# SCH_A320_OVHD_Lights_2023-04-26.net
KiCad netlist of a schematic drawn in EasyEDA
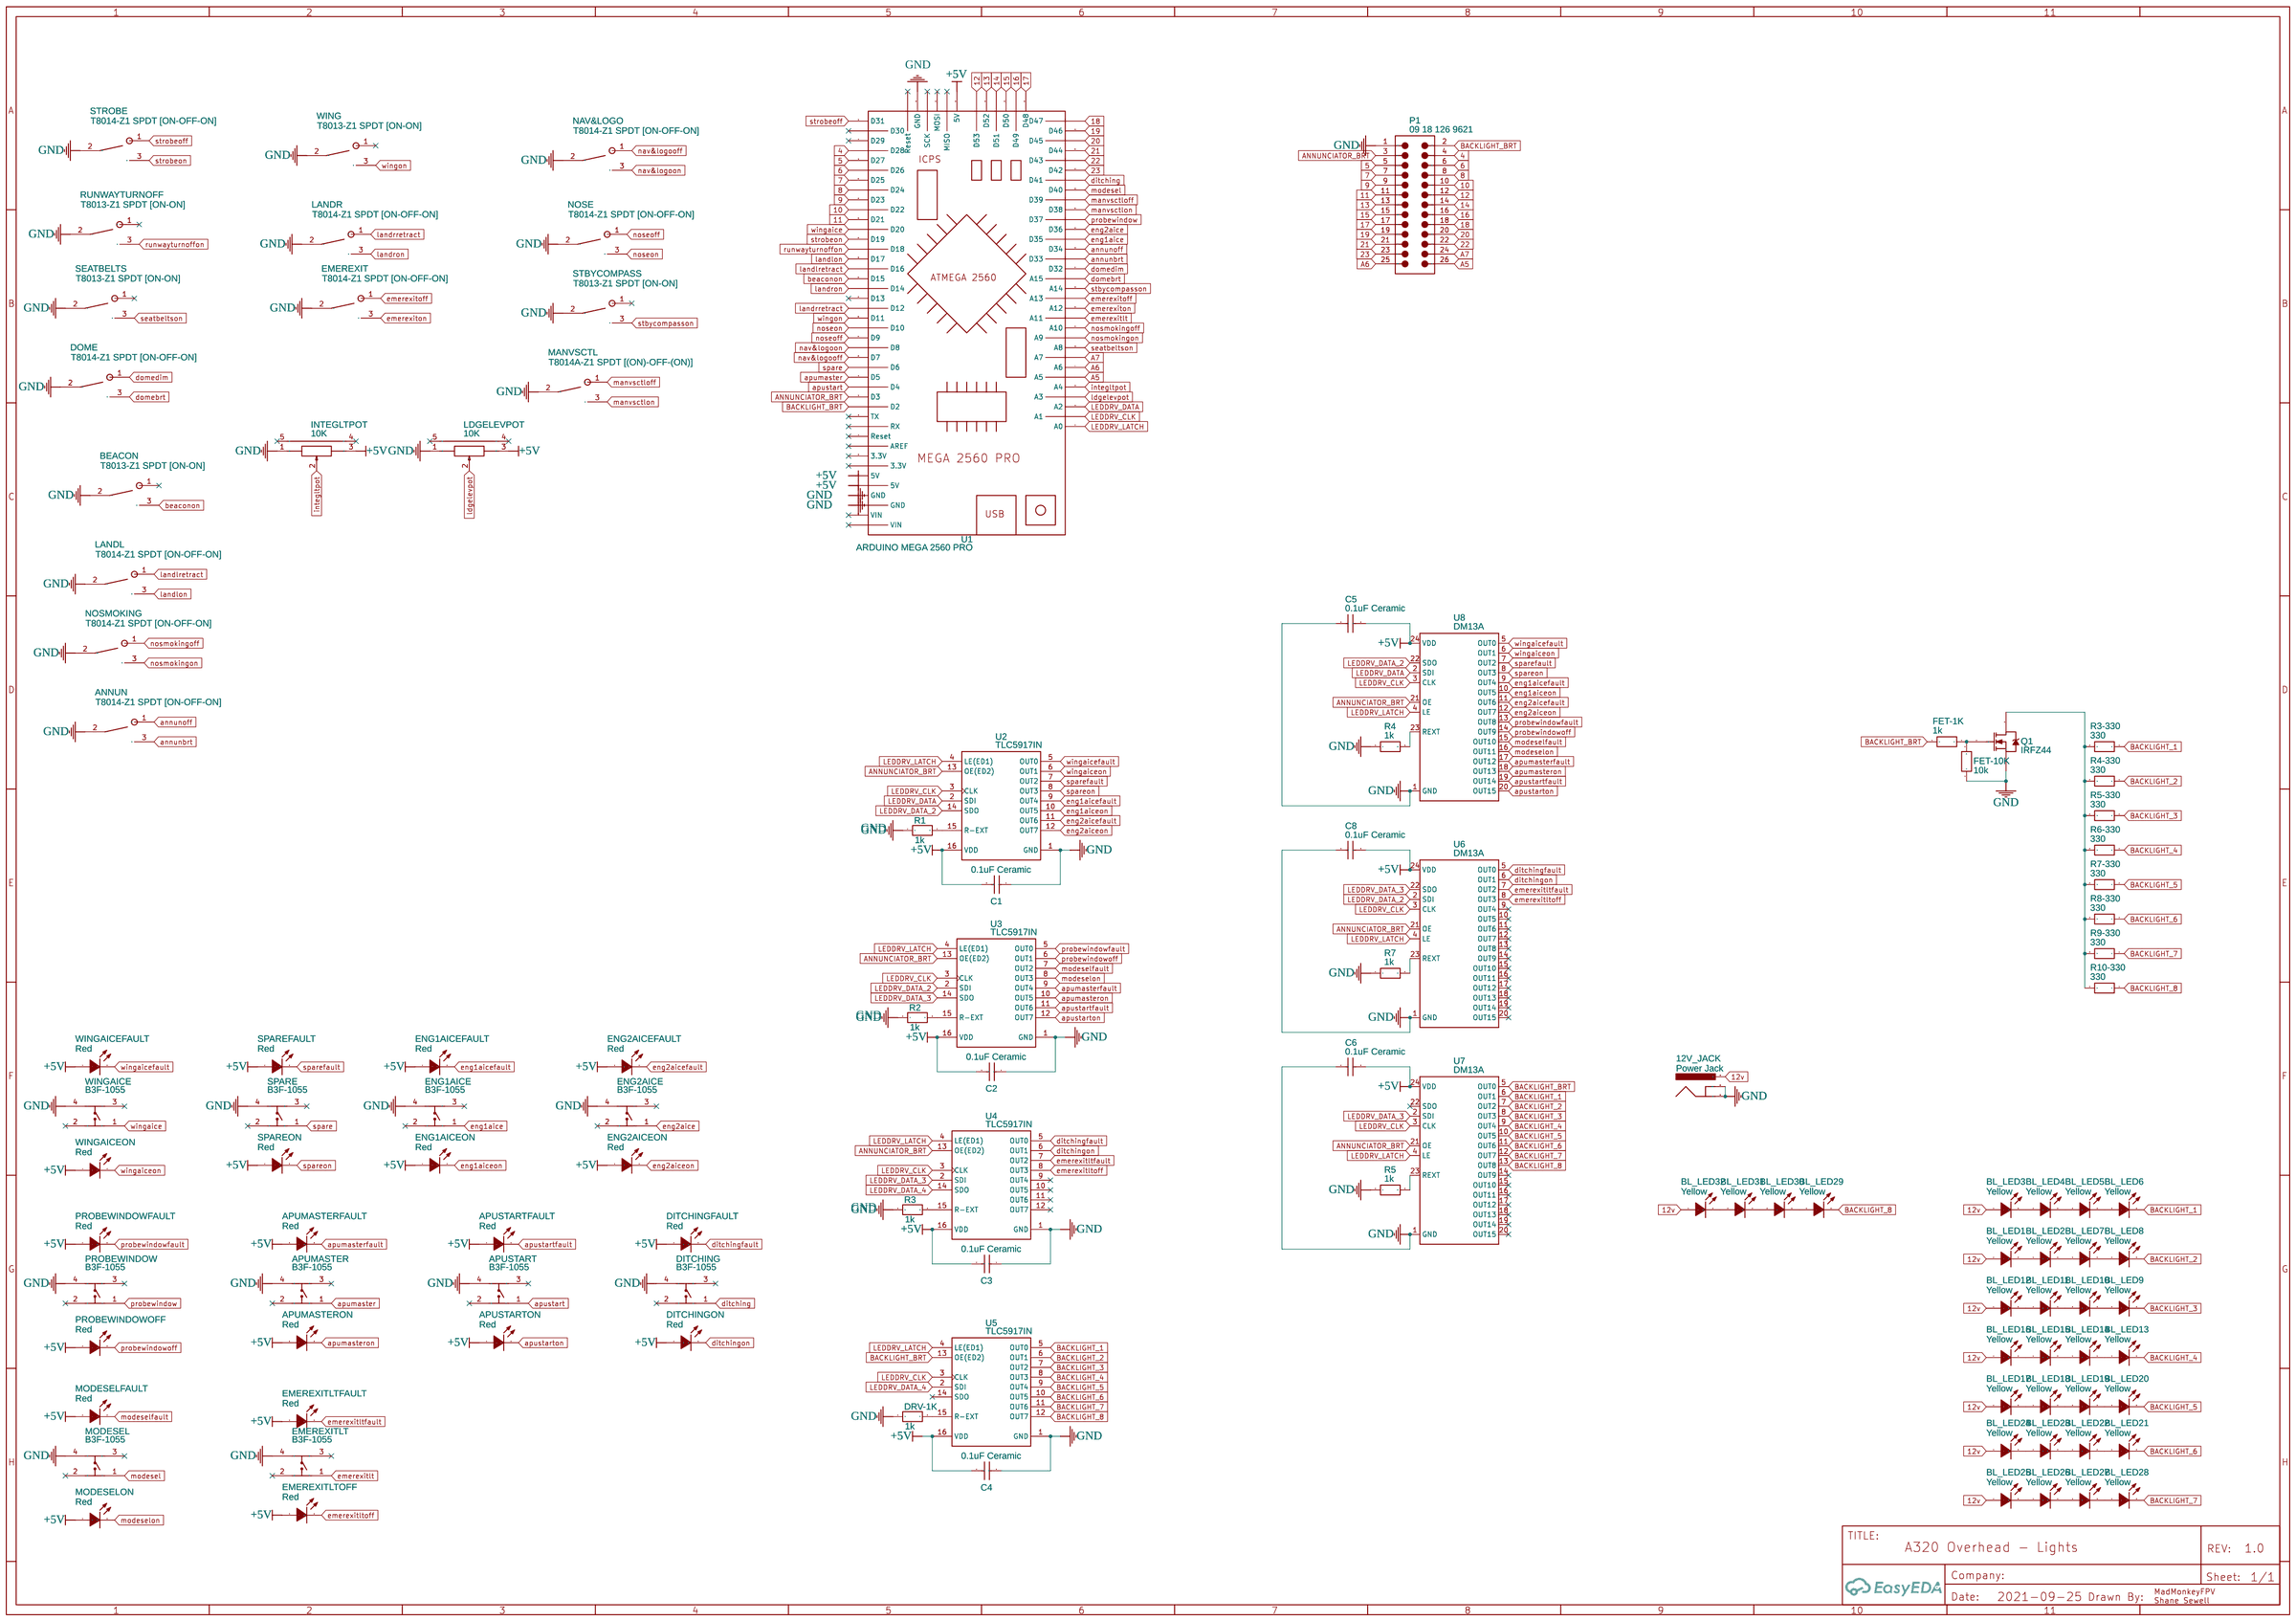
[diagram p0: schematic sheet]

(export (version "E")
  (design (tool "Eeschema 10.0.6"))
  (components
    (comp (ref "12V_JACK")
      (value "Power Jack")
      (fields (field (name "BOM_Supplier Part") "A-4118"))
      (libsource (lib "") (part "POWER_JACK"))
    )
    (comp (ref "ANNUN")
      (value "T8014-Z1 SPDT [ON-OFF-ON]")
      (libsource (lib "") (part "T8014-LK SPDT [ON-OFF-ON]_14"))
    )
    (comp (ref "APUMASTER")
      (value "B3F-1055")
      (fields (field (name "BOM_Manufacturer Part") "B3F-1052") (field (name "BOM_Supplier Part") "C87037"))
      (libsource (lib "") (part "B3F-1055_2"))
    )
    (comp (ref "APUMASTERFAULT")
      (value "Red")
      (fields
        (field (name "BOM_Manufacturer Part") "204-10SDRD/S530-A3-L")
        (field (name "BOM_Supplier Part") "C84774")
      )
      (libsource (lib "") (part "LED-TH-3mm_R_9"))
    )
    (comp (ref "APUMASTERON")
      (value "Red")
      (fields
        (field (name "BOM_Manufacturer Part") "204-10SDRD/S530-A3-L")
        (field (name "BOM_Supplier Part") "C84774")
      )
      (libsource (lib "") (part "LED-TH-3mm_R_7"))
    )
    (comp (ref "APUSTART")
      (value "B3F-1055")
      (fields (field (name "BOM_Manufacturer Part") "B3F-1052") (field (name "BOM_Supplier Part") "C87037"))
      (libsource (lib "") (part "B3F-1055_5"))
    )
    (comp (ref "APUSTARTFAULT")
      (value "Red")
      (fields
        (field (name "BOM_Manufacturer Part") "204-10SDRD/S530-A3-L")
        (field (name "BOM_Supplier Part") "C84774")
      )
      (libsource (lib "") (part "LED-TH-3mm_R"))
    )
    (comp (ref "APUSTARTON")
      (value "Red")
      (fields
        (field (name "BOM_Manufacturer Part") "204-10SDRD/S530-A3-L")
        (field (name "BOM_Supplier Part") "C84774")
      )
      (libsource (lib "") (part "LED-TH-3mm_R_14"))
    )
    (comp (ref "BEACON")
      (value "T8013-Z1 SPDT [ON-ON]")
      (libsource (lib "") (part "T8014-LK SPDT [ON-OFF-ON]_11"))
    )
    (comp (ref "BL_LED1")
      (value "Yellow")
      (fields
        (field (name "BOM_Manufacturer Part") "204-10SDRD/S530-A3-L")
        (field (name "BOM_Supplier Part") "C84774")
      )
      (libsource (lib "") (part "LED-TH-3mm_R_1"))
    )
    (comp (ref "BL_LED2")
      (value "Yellow")
      (fields
        (field (name "BOM_Manufacturer Part") "204-10SDRD/S530-A3-L")
        (field (name "BOM_Supplier Part") "C84774")
      )
      (libsource (lib "") (part "LED-TH-3mm_R_1"))
    )
    (comp (ref "BL_LED3")
      (value "Yellow")
      (fields
        (field (name "BOM_Manufacturer Part") "204-10SDRD/S530-A3-L")
        (field (name "BOM_Supplier Part") "C84774")
      )
      (libsource (lib "") (part "LED-TH-3mm_R_1"))
    )
    (comp (ref "BL_LED4")
      (value "Yellow")
      (fields
        (field (name "BOM_Manufacturer Part") "204-10SDRD/S530-A3-L")
        (field (name "BOM_Supplier Part") "C84774")
      )
      (libsource (lib "") (part "LED-TH-3mm_R_1"))
    )
    (comp (ref "BL_LED5")
      (value "Yellow")
      (fields
        (field (name "BOM_Manufacturer Part") "204-10SDRD/S530-A3-L")
        (field (name "BOM_Supplier Part") "C84774")
      )
      (libsource (lib "") (part "LED-TH-3mm_R_1"))
    )
    (comp (ref "BL_LED6")
      (value "Yellow")
      (fields
        (field (name "BOM_Manufacturer Part") "204-10SDRD/S530-A3-L")
        (field (name "BOM_Supplier Part") "C84774")
      )
      (libsource (lib "") (part "LED-TH-3mm_R_1"))
    )
    (comp (ref "BL_LED7")
      (value "Yellow")
      (fields
        (field (name "BOM_Manufacturer Part") "204-10SDRD/S530-A3-L")
        (field (name "BOM_Supplier Part") "C84774")
      )
      (libsource (lib "") (part "LED-TH-3mm_R_1"))
    )
    (comp (ref "BL_LED8")
      (value "Yellow")
      (fields
        (field (name "BOM_Manufacturer Part") "204-10SDRD/S530-A3-L")
        (field (name "BOM_Supplier Part") "C84774")
      )
      (libsource (lib "") (part "LED-TH-3mm_R_1"))
    )
    (comp (ref "BL_LED9")
      (value "Yellow")
      (fields
        (field (name "BOM_Manufacturer Part") "204-10SDRD/S530-A3-L")
        (field (name "BOM_Supplier Part") "C84774")
      )
      (libsource (lib "") (part "LED-TH-3mm_R_1"))
    )
    (comp (ref "BL_LED10")
      (value "Yellow")
      (fields
        (field (name "BOM_Manufacturer Part") "204-10SDRD/S530-A3-L")
        (field (name "BOM_Supplier Part") "C84774")
      )
      (libsource (lib "") (part "LED-TH-3mm_R_1"))
    )
    (comp (ref "BL_LED11")
      (value "Yellow")
      (fields
        (field (name "BOM_Manufacturer Part") "204-10SDRD/S530-A3-L")
        (field (name "BOM_Supplier Part") "C84774")
      )
      (libsource (lib "") (part "LED-TH-3mm_R_1"))
    )
    (comp (ref "BL_LED12")
      (value "Yellow")
      (fields
        (field (name "BOM_Manufacturer Part") "204-10SDRD/S530-A3-L")
        (field (name "BOM_Supplier Part") "C84774")
      )
      (libsource (lib "") (part "LED-TH-3mm_R_1"))
    )
    (comp (ref "BL_LED13")
      (value "Yellow")
      (fields
        (field (name "BOM_Manufacturer Part") "204-10SDRD/S530-A3-L")
        (field (name "BOM_Supplier Part") "C84774")
      )
      (libsource (lib "") (part "LED-TH-3mm_R_1"))
    )
    (comp (ref "BL_LED14")
      (value "Yellow")
      (fields
        (field (name "BOM_Manufacturer Part") "204-10SDRD/S530-A3-L")
        (field (name "BOM_Supplier Part") "C84774")
      )
      (libsource (lib "") (part "LED-TH-3mm_R_1"))
    )
    (comp (ref "BL_LED15")
      (value "Yellow")
      (fields
        (field (name "BOM_Manufacturer Part") "204-10SDRD/S530-A3-L")
        (field (name "BOM_Supplier Part") "C84774")
      )
      (libsource (lib "") (part "LED-TH-3mm_R_1"))
    )
    (comp (ref "BL_LED16")
      (value "Yellow")
      (fields
        (field (name "BOM_Manufacturer Part") "204-10SDRD/S530-A3-L")
        (field (name "BOM_Supplier Part") "C84774")
      )
      (libsource (lib "") (part "LED-TH-3mm_R_1"))
    )
    (comp (ref "BL_LED17")
      (value "Yellow")
      (fields
        (field (name "BOM_Manufacturer Part") "204-10SDRD/S530-A3-L")
        (field (name "BOM_Supplier Part") "C84774")
      )
      (libsource (lib "") (part "LED-TH-3mm_R_1"))
    )
    (comp (ref "BL_LED18")
      (value "Yellow")
      (fields
        (field (name "BOM_Manufacturer Part") "204-10SDRD/S530-A3-L")
        (field (name "BOM_Supplier Part") "C84774")
      )
      (libsource (lib "") (part "LED-TH-3mm_R_1"))
    )
    (comp (ref "BL_LED19")
      (value "Yellow")
      (fields
        (field (name "BOM_Manufacturer Part") "204-10SDRD/S530-A3-L")
        (field (name "BOM_Supplier Part") "C84774")
      )
      (libsource (lib "") (part "LED-TH-3mm_R_1"))
    )
    (comp (ref "BL_LED20")
      (value "Yellow")
      (fields
        (field (name "BOM_Manufacturer Part") "204-10SDRD/S530-A3-L")
        (field (name "BOM_Supplier Part") "C84774")
      )
      (libsource (lib "") (part "LED-TH-3mm_R_1"))
    )
    (comp (ref "BL_LED21")
      (value "Yellow")
      (fields
        (field (name "BOM_Manufacturer Part") "204-10SDRD/S530-A3-L")
        (field (name "BOM_Supplier Part") "C84774")
      )
      (libsource (lib "") (part "LED-TH-3mm_R_1"))
    )
    (comp (ref "BL_LED22")
      (value "Yellow")
      (fields
        (field (name "BOM_Manufacturer Part") "204-10SDRD/S530-A3-L")
        (field (name "BOM_Supplier Part") "C84774")
      )
      (libsource (lib "") (part "LED-TH-3mm_R_1"))
    )
    (comp (ref "BL_LED23")
      (value "Yellow")
      (fields
        (field (name "BOM_Manufacturer Part") "204-10SDRD/S530-A3-L")
        (field (name "BOM_Supplier Part") "C84774")
      )
      (libsource (lib "") (part "LED-TH-3mm_R_1"))
    )
    (comp (ref "BL_LED24")
      (value "Yellow")
      (fields
        (field (name "BOM_Manufacturer Part") "204-10SDRD/S530-A3-L")
        (field (name "BOM_Supplier Part") "C84774")
      )
      (libsource (lib "") (part "LED-TH-3mm_R_1"))
    )
    (comp (ref "BL_LED25")
      (value "Yellow")
      (fields
        (field (name "BOM_Manufacturer Part") "204-10SDRD/S530-A3-L")
        (field (name "BOM_Supplier Part") "C84774")
      )
      (libsource (lib "") (part "LED-TH-3mm_R_1"))
    )
    (comp (ref "BL_LED26")
      (value "Yellow")
      (fields
        (field (name "BOM_Manufacturer Part") "204-10SDRD/S530-A3-L")
        (field (name "BOM_Supplier Part") "C84774")
      )
      (libsource (lib "") (part "LED-TH-3mm_R_1"))
    )
    (comp (ref "BL_LED27")
      (value "Yellow")
      (fields
        (field (name "BOM_Manufacturer Part") "204-10SDRD/S530-A3-L")
        (field (name "BOM_Supplier Part") "C84774")
      )
      (libsource (lib "") (part "LED-TH-3mm_R_1"))
    )
    (comp (ref "BL_LED28")
      (value "Yellow")
      (fields
        (field (name "BOM_Manufacturer Part") "204-10SDRD/S530-A3-L")
        (field (name "BOM_Supplier Part") "C84774")
      )
      (libsource (lib "") (part "LED-TH-3mm_R_1"))
    )
    (comp (ref "BL_LED29")
      (value "Yellow")
      (fields
        (field (name "BOM_Manufacturer Part") "204-10SDRD/S530-A3-L")
        (field (name "BOM_Supplier Part") "C84774")
      )
      (libsource (lib "") (part "LED-TH-3mm_R_1"))
    )
    (comp (ref "BL_LED30")
      (value "Yellow")
      (fields
        (field (name "BOM_Manufacturer Part") "204-10SDRD/S530-A3-L")
        (field (name "BOM_Supplier Part") "C84774")
      )
      (libsource (lib "") (part "LED-TH-3mm_R_1"))
    )
    (comp (ref "BL_LED31")
      (value "Yellow")
      (fields
        (field (name "BOM_Manufacturer Part") "204-10SDRD/S530-A3-L")
        (field (name "BOM_Supplier Part") "C84774")
      )
      (libsource (lib "") (part "LED-TH-3mm_R_1"))
    )
    (comp (ref "BL_LED32")
      (value "Yellow")
      (fields
        (field (name "BOM_Manufacturer Part") "204-10SDRD/S530-A3-L")
        (field (name "BOM_Supplier Part") "C84774")
      )
      (libsource (lib "") (part "LED-TH-3mm_R_1"))
    )
    (comp (ref "C1")
      (value "0.1uF Ceramic")
      (fields (field (name "BOM_Manufacturer Part") "Capacitor_Ceramic"))
      (libsource (lib "") (part "Capacitor_Ceramic"))
    )
    (comp (ref "C2")
      (value "0.1uF Ceramic")
      (fields (field (name "BOM_Manufacturer Part") "Capacitor_Ceramic"))
      (libsource (lib "") (part "Capacitor_Ceramic"))
    )
    (comp (ref "C3")
      (value "0.1uF Ceramic")
      (fields (field (name "BOM_Manufacturer Part") "Capacitor_Ceramic"))
      (libsource (lib "") (part "Capacitor_Ceramic"))
    )
    (comp (ref "C4")
      (value "0.1uF Ceramic")
      (fields (field (name "BOM_Manufacturer Part") "Capacitor_Ceramic"))
      (libsource (lib "") (part "Capacitor_Ceramic"))
    )
    (comp (ref "C5")
      (value "0.1uF Ceramic")
      (fields (field (name "BOM_Manufacturer Part") "Capacitor_Ceramic"))
      (libsource (lib "") (part "Capacitor_Ceramic_1"))
    )
    (comp (ref "C6")
      (value "0.1uF Ceramic")
      (fields (field (name "BOM_Manufacturer Part") "Capacitor_Ceramic"))
      (libsource (lib "") (part "Capacitor_Ceramic_1"))
    )
    (comp (ref "C8")
      (value "0.1uF Ceramic")
      (fields (field (name "BOM_Manufacturer Part") "Capacitor_Ceramic"))
      (libsource (lib "") (part "Capacitor_Ceramic_1"))
    )
    (comp (ref "DITCHING")
      (value "B3F-1055")
      (fields (field (name "BOM_Manufacturer Part") "B3F-1052") (field (name "BOM_Supplier Part") "C87037"))
      (libsource (lib "") (part "B3F-1055_1"))
    )
    (comp (ref "DITCHINGFAULT")
      (value "Red")
      (fields
        (field (name "BOM_Manufacturer Part") "204-10SDRD/S530-A3-L")
        (field (name "BOM_Supplier Part") "C84774")
      )
      (libsource (lib "") (part "LED-TH-3mm_R_18"))
    )
    (comp (ref "DITCHINGON")
      (value "Red")
      (fields
        (field (name "BOM_Manufacturer Part") "204-10SDRD/S530-A3-L")
        (field (name "BOM_Supplier Part") "C84774")
      )
      (libsource (lib "") (part "LED-TH-3mm_R_19"))
    )
    (comp (ref "DOME")
      (value "T8014-Z1 SPDT [ON-OFF-ON]")
      (libsource (lib "") (part "T8014-LK SPDT [ON-OFF-ON]_8"))
    )
    (comp (ref "DRV-1K") (value "1k") (libsource (lib "") (part "R_AXIAL-0.3_EU_8")))
    (comp (ref "EMEREXIT")
      (value "T8014-Z1 SPDT [ON-OFF-ON]")
      (libsource (lib "") (part "T8014-LK SPDT [ON-OFF-ON]_2"))
    )
    (comp (ref "EMEREXITLT")
      (value "B3F-1055")
      (fields (field (name "BOM_Manufacturer Part") "B3F-1052") (field (name "BOM_Supplier Part") "C87037"))
      (libsource (lib "") (part "B3F-1055_9"))
    )
    (comp (ref "EMEREXITLTFAULT")
      (value "Red")
      (fields
        (field (name "BOM_Manufacturer Part") "204-10SDRD/S530-A3-L")
        (field (name "BOM_Supplier Part") "C84774")
      )
      (libsource (lib "") (part "LED-TH-3mm_R_12"))
    )
    (comp (ref "EMEREXITLTOFF")
      (value "Red")
      (fields
        (field (name "BOM_Manufacturer Part") "204-10SDRD/S530-A3-L")
        (field (name "BOM_Supplier Part") "C84774")
      )
      (libsource (lib "") (part "LED-TH-3mm_R_6"))
    )
    (comp (ref "ENG1AICE")
      (value "B3F-1055")
      (fields (field (name "BOM_Manufacturer Part") "B3F-1052") (field (name "BOM_Supplier Part") "C87037"))
      (libsource (lib "") (part "B3F-1055"))
    )
    (comp (ref "ENG1AICEFAULT")
      (value "Red")
      (fields
        (field (name "BOM_Manufacturer Part") "204-10SDRD/S530-A3-L")
        (field (name "BOM_Supplier Part") "C84774")
      )
      (libsource (lib "") (part "LED-TH-3mm_R_5"))
    )
    (comp (ref "ENG1AICEON")
      (value "Red")
      (fields
        (field (name "BOM_Manufacturer Part") "204-10SDRD/S530-A3-L")
        (field (name "BOM_Supplier Part") "C84774")
      )
      (libsource (lib "") (part "LED-TH-3mm_R_11"))
    )
    (comp (ref "ENG2AICE")
      (value "B3F-1055")
      (fields (field (name "BOM_Manufacturer Part") "B3F-1052") (field (name "BOM_Supplier Part") "C87037"))
      (libsource (lib "") (part "B3F-1055_6"))
    )
    (comp (ref "ENG2AICEFAULT")
      (value "Red")
      (fields
        (field (name "BOM_Manufacturer Part") "204-10SDRD/S530-A3-L")
        (field (name "BOM_Supplier Part") "C84774")
      )
      (libsource (lib "") (part "LED-TH-3mm_R_15"))
    )
    (comp (ref "ENG2AICEON")
      (value "Red")
      (fields
        (field (name "BOM_Manufacturer Part") "204-10SDRD/S530-A3-L")
        (field (name "BOM_Supplier Part") "C84774")
      )
      (libsource (lib "") (part "LED-TH-3mm_R_13"))
    )
    (comp (ref "FET-1K") (value "1k") (libsource (lib "") (part "R_AXIAL-0.3_EU_4")))
    (comp (ref "FET-10K") (value "10k") (libsource (lib "") (part "R_AXIAL-0.3_EU_11")))
    (comp (ref "INTEGLTPOT")
      (value "10K")
      (fields
        (field (name "BOM_Manufacturer Part") "RK09K1130A70")
        (field (name "BOM_Supplier Part") "C351173")
      )
      (libsource (lib "") (part "RK09K1130A70"))
    )
    (comp (ref "LANDL")
      (value "T8014-Z1 SPDT [ON-OFF-ON]")
      (libsource (lib "") (part "T8014-LK SPDT [ON-OFF-ON]_7"))
    )
    (comp (ref "LANDR")
      (value "T8014-Z1 SPDT [ON-OFF-ON]")
      (libsource (lib "") (part "T8014-LK SPDT [ON-OFF-ON]_6"))
    )
    (comp (ref "LDGELEVPOT")
      (value "10K")
      (fields
        (field (name "BOM_Manufacturer Part") "RK09K1130A70")
        (field (name "BOM_Supplier Part") "C351173")
      )
      (libsource (lib "") (part "RK09K1130A70_1"))
    )
    (comp (ref "MANVSCTL")
      (value "T8014A-Z1 SPDT [(ON)-OFF-(ON)]")
      (libsource (lib "") (part "T8014-LK SPDT [ON-OFF-ON]_4"))
    )
    (comp (ref "MODESEL")
      (value "B3F-1055")
      (fields (field (name "BOM_Manufacturer Part") "B3F-1052") (field (name "BOM_Supplier Part") "C87037"))
      (libsource (lib "") (part "B3F-1055_4"))
    )
    (comp (ref "MODESELFAULT")
      (value "Red")
      (fields
        (field (name "BOM_Manufacturer Part") "204-10SDRD/S530-A3-L")
        (field (name "BOM_Supplier Part") "C84774")
      )
      (libsource (lib "") (part "LED-TH-3mm_R_3"))
    )
    (comp (ref "MODESELON")
      (value "Red")
      (fields
        (field (name "BOM_Manufacturer Part") "204-10SDRD/S530-A3-L")
        (field (name "BOM_Supplier Part") "C84774")
      )
      (libsource (lib "") (part "LED-TH-3mm_R_16"))
    )
    (comp (ref "NAV&LOGO")
      (value "T8014-Z1 SPDT [ON-OFF-ON]")
      (libsource (lib "") (part "T8014-LK SPDT [ON-OFF-ON]_9"))
    )
    (comp (ref "NOSE")
      (value "T8014-Z1 SPDT [ON-OFF-ON]")
      (libsource (lib "") (part "T8014-LK SPDT [ON-OFF-ON]_12"))
    )
    (comp (ref "NOSMOKING")
      (value "T8014-Z1 SPDT [ON-OFF-ON]")
      (libsource (lib "") (part "T8014-LK SPDT [ON-OFF-ON]_13"))
    )
    (comp (ref "P1") (value "09 18 126 9621") (libsource (lib "") (part "09 18 126 9621")))
    (comp (ref "PROBEWINDOW")
      (value "B3F-1055")
      (fields (field (name "BOM_Manufacturer Part") "B3F-1052") (field (name "BOM_Supplier Part") "C87037"))
      (libsource (lib "") (part "B3F-1055_3"))
    )
    (comp (ref "PROBEWINDOWFAULT")
      (value "Red")
      (fields
        (field (name "BOM_Manufacturer Part") "204-10SDRD/S530-A3-L")
        (field (name "BOM_Supplier Part") "C84774")
      )
      (libsource (lib "") (part "LED-TH-3mm_R_2"))
    )
    (comp (ref "PROBEWINDOWOFF")
      (value "Red")
      (fields
        (field (name "BOM_Manufacturer Part") "204-10SDRD/S530-A3-L")
        (field (name "BOM_Supplier Part") "C84774")
      )
      (libsource (lib "") (part "LED-TH-3mm_R_17"))
    )
    (comp (ref "Q1") (value "IRFZ44") (libsource (lib "") (part "IRFZ44")))
    (comp (ref "R1") (value "1k") (libsource (lib "") (part "R_AXIAL-0.3_EU")))
    (comp (ref "R2") (value "1k") (libsource (lib "") (part "R_AXIAL-0.3_EU")))
    (comp (ref "R3") (value "1k") (libsource (lib "") (part "R_AXIAL-0.3_EU")))
    (comp (ref "R3-330") (value "330") (libsource (lib "") (part "R_AXIAL-0.3_EU_5")))
    (comp (ref "R4") (value "1k") (libsource (lib "") (part "R_AXIAL-0.3_EU")))
    (comp (ref "R4-330") (value "330") (libsource (lib "") (part "R_AXIAL-0.3_EU_2")))
    (comp (ref "R5") (value "1k") (libsource (lib "") (part "R_AXIAL-0.3_EU")))
    (comp (ref "R5-330") (value "330") (libsource (lib "") (part "R_AXIAL-0.3_EU_7")))
    (comp (ref "R6-330") (value "330") (libsource (lib "") (part "R_AXIAL-0.3_EU_9")))
    (comp (ref "R7") (value "1k") (libsource (lib "") (part "R_AXIAL-0.3_EU")))
    (comp (ref "R7-330") (value "330") (libsource (lib "") (part "R_AXIAL-0.3_EU_1")))
    (comp (ref "R8-330") (value "330") (libsource (lib "") (part "R_AXIAL-0.3_EU_3")))
    (comp (ref "R9-330") (value "330") (libsource (lib "") (part "R_AXIAL-0.3_EU_10")))
    (comp (ref "R10-330") (value "330") (libsource (lib "") (part "R_AXIAL-0.3_EU_6")))
    (comp (ref "RUNWAYTURNOFF")
      (value "T8013-Z1 SPDT [ON-ON]")
      (libsource (lib "") (part "T8014-LK SPDT [ON-OFF-ON]_5"))
    )
    (comp (ref "SEATBELTS")
      (value "T8013-Z1 SPDT [ON-ON]")
      (libsource (lib "") (part "T8014-LK SPDT [ON-OFF-ON]"))
    )
    (comp (ref "SPARE")
      (value "B3F-1055")
      (fields (field (name "BOM_Manufacturer Part") "B3F-1052") (field (name "BOM_Supplier Part") "C87037"))
      (libsource (lib "") (part "B3F-1055_8"))
    )
    (comp (ref "SPAREFAULT")
      (value "Red")
      (fields
        (field (name "BOM_Manufacturer Part") "204-10SDRD/S530-A3-L")
        (field (name "BOM_Supplier Part") "C84774")
      )
      (libsource (lib "") (part "LED-TH-3mm_R_4"))
    )
    (comp (ref "SPAREON")
      (value "Red")
      (fields
        (field (name "BOM_Manufacturer Part") "204-10SDRD/S530-A3-L")
        (field (name "BOM_Supplier Part") "C84774")
      )
      (libsource (lib "") (part "LED-TH-3mm_R_10"))
    )
    (comp (ref "STBYCOMPASS")
      (value "T8013-Z1 SPDT [ON-ON]")
      (libsource (lib "") (part "T8014-LK SPDT [ON-OFF-ON]_3"))
    )
    (comp (ref "STROBE")
      (value "T8014-Z1 SPDT [ON-OFF-ON]")
      (libsource (lib "") (part "T8014-LK SPDT [ON-OFF-ON]_10"))
    )
    (comp (ref "U1")
      (value "ARDUINO MEGA 2560 PRO")
      (fields (field (name "BOM_Manufacturer Part") "Arduino Mega 2560 Pro Mini"))
      (libsource (lib "") (part "ARDUINO MEGA 2560 PRO"))
    )
    (comp (ref "U2") (value "TLC5917IN") (libsource (lib "") (part "TLC5917IN")))
    (comp (ref "U3") (value "TLC5917IN") (libsource (lib "") (part "TLC5917IN")))
    (comp (ref "U4") (value "TLC5917IN") (libsource (lib "") (part "TLC5917IN")))
    (comp (ref "U5") (value "TLC5917IN") (libsource (lib "") (part "TLC5917IN")))
    (comp (ref "U6") (value "DM13A") (libsource (lib "") (part "DM13A")))
    (comp (ref "U7") (value "DM13A") (libsource (lib "") (part "DM13A")))
    (comp (ref "U8") (value "DM13A") (libsource (lib "") (part "DM13A")))
    (comp (ref "WING")
      (value "T8013-Z1 SPDT [ON-ON]")
      (libsource (lib "") (part "T8014-LK SPDT [ON-OFF-ON]_1"))
    )
    (comp (ref "WINGAICE")
      (value "B3F-1055")
      (fields (field (name "BOM_Manufacturer Part") "B3F-1052") (field (name "BOM_Supplier Part") "C87037"))
      (libsource (lib "") (part "B3F-1055_7"))
    )
    (comp (ref "WINGAICEFAULT")
      (value "Red")
      (fields
        (field (name "BOM_Manufacturer Part") "204-10SDRD/S530-A3-L")
        (field (name "BOM_Supplier Part") "C84774")
      )
      (libsource (lib "") (part "LED-TH-3mm_R_20"))
    )
    (comp (ref "WINGAICEON")
      (value "Red")
      (fields
        (field (name "BOM_Manufacturer Part") "204-10SDRD/S530-A3-L")
        (field (name "BOM_Supplier Part") "C84774")
      )
      (libsource (lib "") (part "LED-TH-3mm_R_8"))
    )
  )
  (nets
    (net (code "1") (name "+5V") (class "Default")
      (node (ref "APUMASTERFAULT") (pin "1") (pinfunction "1_1") (pintype "unspecified"))
      (node (ref "APUMASTERON") (pin "1") (pinfunction "1_1") (pintype "unspecified"))
      (node (ref "APUSTARTFAULT") (pin "1") (pinfunction "1_1") (pintype "unspecified"))
      (node (ref "APUSTARTON") (pin "1") (pinfunction "1_1") (pintype "unspecified"))
      (node (ref "C1") (pin "2") (pinfunction "2_2") (pintype "unspecified"))
      (node (ref "C2") (pin "2") (pinfunction "2_2") (pintype "unspecified"))
      (node (ref "C3") (pin "2") (pinfunction "2_2") (pintype "unspecified"))
      (node (ref "C4") (pin "2") (pinfunction "2_2") (pintype "unspecified"))
      (node (ref "C5") (pin "2") (pinfunction "2_2") (pintype "unspecified"))
      (node (ref "C6") (pin "2") (pinfunction "2_2") (pintype "unspecified"))
      (node (ref "C8") (pin "2") (pinfunction "2_2") (pintype "unspecified"))
      (node (ref "DITCHINGFAULT") (pin "1") (pinfunction "1_1") (pintype "unspecified"))
      (node (ref "DITCHINGON") (pin "1") (pinfunction "1_1") (pintype "unspecified"))
      (node (ref "EMEREXITLTFAULT") (pin "1") (pinfunction "1_1") (pintype "unspecified"))
      (node (ref "EMEREXITLTOFF") (pin "1") (pinfunction "1_1") (pintype "unspecified"))
      (node (ref "ENG1AICEFAULT") (pin "1") (pinfunction "1_1") (pintype "unspecified"))
      (node (ref "ENG1AICEON") (pin "1") (pinfunction "1_1") (pintype "unspecified"))
      (node (ref "ENG2AICEFAULT") (pin "1") (pinfunction "1_1") (pintype "unspecified"))
      (node (ref "ENG2AICEON") (pin "1") (pinfunction "1_1") (pintype "unspecified"))
      (node (ref "INTEGLTPOT") (pin "3") (pinfunction "3_3") (pintype "unspecified"))
      (node (ref "LDGELEVPOT") (pin "3") (pinfunction "3_3") (pintype "unspecified"))
      (node (ref "MODESELFAULT") (pin "1") (pinfunction "1_1") (pintype "unspecified"))
      (node (ref "MODESELON") (pin "1") (pinfunction "1_1") (pintype "unspecified"))
      (node (ref "PROBEWINDOWFAULT") (pin "1") (pinfunction "1_1") (pintype "unspecified"))
      (node (ref "PROBEWINDOWOFF") (pin "1") (pinfunction "1_1") (pintype "unspecified"))
      (node (ref "SPAREFAULT") (pin "1") (pinfunction "1_1") (pintype "unspecified"))
      (node (ref "SPAREON") (pin "1") (pinfunction "1_1") (pintype "unspecified"))
      (node (ref "U1") (pin "39") (pinfunction "5V_39") (pintype "unspecified"))
      (node (ref "U1") (pin "81") (pinfunction "5V_81") (pintype "unspecified"))
      (node (ref "U1") (pin "82") (pinfunction "5V_82") (pintype "unspecified"))
      (node (ref "U2") (pin "16") (pinfunction "VDD_16") (pintype "passive"))
      (node (ref "U3") (pin "16") (pinfunction "VDD_16") (pintype "passive"))
      (node (ref "U4") (pin "16") (pinfunction "VDD_16") (pintype "passive"))
      (node (ref "U5") (pin "16") (pinfunction "VDD_16") (pintype "passive"))
      (node (ref "U6") (pin "24") (pinfunction "VDD_24") (pintype "unspecified"))
      (node (ref "U7") (pin "24") (pinfunction "VDD_24") (pintype "unspecified"))
      (node (ref "U8") (pin "24") (pinfunction "VDD_24") (pintype "unspecified"))
      (node (ref "WINGAICEFAULT") (pin "1") (pinfunction "1_1") (pintype "unspecified"))
      (node (ref "WINGAICEON") (pin "1") (pinfunction "1_1") (pintype "unspecified"))
    )
    (net (code "2") (name "4") (class "Default")
      (node (ref "P1") (pin "4") (pinfunction "4_4") (pintype "unspecified"))
      (node (ref "U1") (pin "48") (pinfunction "D28_48") (pintype "unspecified"))
    )
    (net (code "3") (name "5") (class "Default")
      (node (ref "P1") (pin "5") (pinfunction "5_5") (pintype "unspecified"))
      (node (ref "U1") (pin "49") (pinfunction "D27_49") (pintype "unspecified"))
    )
    (net (code "4") (name "6") (class "Default")
      (node (ref "P1") (pin "6") (pinfunction "6_6") (pintype "unspecified"))
      (node (ref "U1") (pin "50") (pinfunction "D26_50") (pintype "unspecified"))
    )
    (net (code "5") (name "7") (class "Default")
      (node (ref "P1") (pin "7") (pinfunction "7_7") (pintype "unspecified"))
      (node (ref "U1") (pin "51") (pinfunction "D25_51") (pintype "unspecified"))
    )
    (net (code "6") (name "8") (class "Default")
      (node (ref "P1") (pin "8") (pinfunction "8_8") (pintype "unspecified"))
      (node (ref "U1") (pin "52") (pinfunction "D24_52") (pintype "unspecified"))
    )
    (net (code "7") (name "9") (class "Default")
      (node (ref "P1") (pin "9") (pinfunction "9_9") (pintype "unspecified"))
      (node (ref "U1") (pin "53") (pinfunction "D23_53") (pintype "unspecified"))
    )
    (net (code "8") (name "10") (class "Default")
      (node (ref "P1") (pin "10") (pinfunction "10_10") (pintype "unspecified"))
      (node (ref "U1") (pin "54") (pinfunction "D22_54") (pintype "unspecified"))
    )
    (net (code "9") (name "11") (class "Default")
      (node (ref "P1") (pin "11") (pinfunction "11_11") (pintype "unspecified"))
      (node (ref "U1") (pin "55") (pinfunction "D21_55") (pintype "unspecified"))
    )
    (net (code "10") (name "12") (class "Default")
      (node (ref "P1") (pin "12") (pinfunction "12_12") (pintype "unspecified"))
      (node (ref "U1") (pin "38") (pinfunction "D53_38") (pintype "unspecified"))
    )
    (net (code "11") (name "12v") (class "Default")
      (node (ref "12V_JACK") (pin "PWR") (pinfunction "PWR_PWR") (pintype "unspecified"))
      (node (ref "BL_LED1") (pin "1") (pinfunction "1_1") (pintype "unspecified"))
      (node (ref "BL_LED12") (pin "1") (pinfunction "1_1") (pintype "unspecified"))
      (node (ref "BL_LED16") (pin "1") (pinfunction "1_1") (pintype "unspecified"))
      (node (ref "BL_LED17") (pin "1") (pinfunction "1_1") (pintype "unspecified"))
      (node (ref "BL_LED24") (pin "1") (pinfunction "1_1") (pintype "unspecified"))
      (node (ref "BL_LED25") (pin "1") (pinfunction "1_1") (pintype "unspecified"))
      (node (ref "BL_LED3") (pin "1") (pinfunction "1_1") (pintype "unspecified"))
      (node (ref "BL_LED32") (pin "1") (pinfunction "1_1") (pintype "unspecified"))
    )
    (net (code "12") (name "13") (class "Default")
      (node (ref "P1") (pin "13") (pinfunction "13_13") (pintype "unspecified"))
      (node (ref "U1") (pin "37") (pinfunction "D52_37") (pintype "unspecified"))
    )
    (net (code "13") (name "14") (class "Default")
      (node (ref "P1") (pin "14") (pinfunction "14_14") (pintype "unspecified"))
      (node (ref "U1") (pin "36") (pinfunction "D51_36") (pintype "unspecified"))
    )
    (net (code "14") (name "15") (class "Default")
      (node (ref "P1") (pin "15") (pinfunction "15_15") (pintype "unspecified"))
      (node (ref "U1") (pin "35") (pinfunction "D50_35") (pintype "unspecified"))
    )
    (net (code "15") (name "16") (class "Default")
      (node (ref "P1") (pin "16") (pinfunction "16_16") (pintype "unspecified"))
      (node (ref "U1") (pin "34") (pinfunction "D49_34") (pintype "unspecified"))
    )
    (net (code "16") (name "17") (class "Default")
      (node (ref "P1") (pin "17") (pinfunction "17_17") (pintype "unspecified"))
      (node (ref "U1") (pin "33") (pinfunction "D48_33") (pintype "unspecified"))
    )
    (net (code "17") (name "18") (class "Default")
      (node (ref "P1") (pin "18") (pinfunction "18_18") (pintype "unspecified"))
      (node (ref "U1") (pin "32") (pinfunction "D47_32") (pintype "unspecified"))
    )
    (net (code "18") (name "19") (class "Default")
      (node (ref "P1") (pin "19") (pinfunction "19_19") (pintype "unspecified"))
      (node (ref "U1") (pin "31") (pinfunction "D46_31") (pintype "unspecified"))
    )
    (net (code "19") (name "20") (class "Default")
      (node (ref "P1") (pin "20") (pinfunction "20_20") (pintype "unspecified"))
      (node (ref "U1") (pin "30") (pinfunction "D45_30") (pintype "unspecified"))
    )
    (net (code "20") (name "21") (class "Default")
      (node (ref "P1") (pin "21") (pinfunction "21_21") (pintype "unspecified"))
      (node (ref "U1") (pin "29") (pinfunction "D44_29") (pintype "unspecified"))
    )
    (net (code "21") (name "22") (class "Default")
      (node (ref "P1") (pin "22") (pinfunction "22_22") (pintype "unspecified"))
      (node (ref "U1") (pin "28") (pinfunction "D43_28") (pintype "unspecified"))
    )
    (net (code "22") (name "23") (class "Default")
      (node (ref "P1") (pin "23") (pinfunction "23_23") (pintype "unspecified"))
      (node (ref "U1") (pin "27") (pinfunction "D42_27") (pintype "unspecified"))
    )
    (net (code "23") (name "A5") (class "Default")
      (node (ref "P1") (pin "26") (pinfunction "A5_26") (pintype "unspecified"))
      (node (ref "U1") (pin "6") (pinfunction "A5_6") (pintype "unspecified"))
    )
    (net (code "24") (name "A6") (class "Default")
      (node (ref "P1") (pin "25") (pinfunction "A6_25") (pintype "unspecified"))
      (node (ref "U1") (pin "7") (pinfunction "A6_7") (pintype "unspecified"))
    )
    (net (code "25") (name "A7") (class "Default")
      (node (ref "P1") (pin "24") (pinfunction "A7_24") (pintype "unspecified"))
      (node (ref "U1") (pin "8") (pinfunction "A7_8") (pintype "unspecified"))
    )
    (net (code "26") (name "ANNUNCIATOR_BRT") (class "Default")
      (node (ref "P1") (pin "3") (pinfunction "3_3") (pintype "unspecified"))
      (node (ref "U1") (pin "73") (pinfunction "D3_73") (pintype "unspecified"))
      (node (ref "U2") (pin "13") (pinfunction "OE(ED2)_13") (pintype "unspecified"))
      (node (ref "U3") (pin "13") (pinfunction "OE(ED2)_13") (pintype "unspecified"))
      (node (ref "U4") (pin "13") (pinfunction "OE(ED2)_13") (pintype "unspecified"))
      (node (ref "U6") (pin "21") (pinfunction "OE_21") (pintype "unspecified"))
      (node (ref "U7") (pin "21") (pinfunction "OE_21") (pintype "unspecified"))
      (node (ref "U8") (pin "21") (pinfunction "OE_21") (pintype "unspecified"))
    )
    (net (code "27") (name "BACKLIGHT_1") (class "Default")
      (node (ref "BL_LED6") (pin "2") (pinfunction "2_2") (pintype "unspecified"))
      (node (ref "R3-330") (pin "1") (pinfunction "1_1") (pintype "unspecified"))
      (node (ref "U5") (pin "5") (pinfunction "OUT0_5") (pintype "output"))
      (node (ref "U7") (pin "6") (pinfunction "OUT1_6") (pintype "unspecified"))
    )
    (net (code "28") (name "BACKLIGHT_2") (class "Default")
      (node (ref "BL_LED8") (pin "2") (pinfunction "2_2") (pintype "unspecified"))
      (node (ref "R4-330") (pin "1") (pinfunction "1_1") (pintype "unspecified"))
      (node (ref "U5") (pin "6") (pinfunction "OUT1_6") (pintype "output"))
      (node (ref "U7") (pin "7") (pinfunction "OUT2_7") (pintype "unspecified"))
    )
    (net (code "29") (name "BACKLIGHT_3") (class "Default")
      (node (ref "BL_LED9") (pin "2") (pinfunction "2_2") (pintype "unspecified"))
      (node (ref "R5-330") (pin "1") (pinfunction "1_1") (pintype "unspecified"))
      (node (ref "U5") (pin "7") (pinfunction "OUT2_7") (pintype "output"))
      (node (ref "U7") (pin "8") (pinfunction "OUT3_8") (pintype "unspecified"))
    )
    (net (code "30") (name "BACKLIGHT_4") (class "Default")
      (node (ref "BL_LED13") (pin "2") (pinfunction "2_2") (pintype "unspecified"))
      (node (ref "R6-330") (pin "1") (pinfunction "1_1") (pintype "unspecified"))
      (node (ref "U5") (pin "8") (pinfunction "OUT3_8") (pintype "output"))
      (node (ref "U7") (pin "9") (pinfunction "OUT4_9") (pintype "unspecified"))
    )
    (net (code "31") (name "BACKLIGHT_5") (class "Default")
      (node (ref "BL_LED20") (pin "2") (pinfunction "2_2") (pintype "unspecified"))
      (node (ref "R7-330") (pin "1") (pinfunction "1_1") (pintype "unspecified"))
      (node (ref "U5") (pin "9") (pinfunction "OUT4_9") (pintype "output"))
      (node (ref "U7") (pin "10") (pinfunction "OUT5_10") (pintype "unspecified"))
    )
    (net (code "32") (name "BACKLIGHT_6") (class "Default")
      (node (ref "BL_LED21") (pin "2") (pinfunction "2_2") (pintype "unspecified"))
      (node (ref "R8-330") (pin "1") (pinfunction "1_1") (pintype "unspecified"))
      (node (ref "U5") (pin "10") (pinfunction "OUT5_10") (pintype "output"))
      (node (ref "U7") (pin "11") (pinfunction "OUT6_11") (pintype "unspecified"))
    )
    (net (code "33") (name "BACKLIGHT_7") (class "Default")
      (node (ref "BL_LED28") (pin "2") (pinfunction "2_2") (pintype "unspecified"))
      (node (ref "R9-330") (pin "1") (pinfunction "1_1") (pintype "unspecified"))
      (node (ref "U5") (pin "11") (pinfunction "OUT6_11") (pintype "output"))
      (node (ref "U7") (pin "12") (pinfunction "OUT7_12") (pintype "unspecified"))
    )
    (net (code "34") (name "BACKLIGHT_8") (class "Default")
      (node (ref "BL_LED29") (pin "2") (pinfunction "2_2") (pintype "unspecified"))
      (node (ref "R10-330") (pin "1") (pinfunction "1_1") (pintype "unspecified"))
      (node (ref "U5") (pin "12") (pinfunction "OUT7_12") (pintype "output"))
      (node (ref "U7") (pin "13") (pinfunction "OUT8_13") (pintype "unspecified"))
    )
    (net (code "35") (name "BACKLIGHT_BRT") (class "Default")
      (node (ref "FET-1K") (pin "2") (pinfunction "2_2") (pintype "unspecified"))
      (node (ref "P1") (pin "2") (pinfunction "2_2") (pintype "unspecified"))
      (node (ref "U1") (pin "74") (pinfunction "D2_74") (pintype "unspecified"))
      (node (ref "U5") (pin "13") (pinfunction "OE(ED2)_13") (pintype "unspecified"))
      (node (ref "U7") (pin "5") (pinfunction "OUT0_5") (pintype "unspecified"))
    )
    (net (code "36") (name "GND") (class "Default")
      (node (ref "12V_JACK") (pin "GND") (pinfunction "GND_GND") (pintype "unspecified"))
      (node (ref "12V_JACK") (pin "GNDBREAK") (pinfunction "GNDBREAK_GNDBREAK") (pintype "unspecified"))
      (node (ref "ANNUN") (pin "2") (pinfunction "2_2") (pintype "input"))
      (node (ref "APUMASTER") (pin "4") (pinfunction "4_4") (pintype "unspecified"))
      (node (ref "APUSTART") (pin "4") (pinfunction "4_4") (pintype "unspecified"))
      (node (ref "BEACON") (pin "2") (pinfunction "2_2") (pintype "input"))
      (node (ref "C1") (pin "1") (pinfunction "1_1") (pintype "unspecified"))
      (node (ref "C2") (pin "1") (pinfunction "1_1") (pintype "unspecified"))
      (node (ref "C3") (pin "1") (pinfunction "1_1") (pintype "unspecified"))
      (node (ref "C4") (pin "1") (pinfunction "1_1") (pintype "unspecified"))
      (node (ref "C5") (pin "1") (pinfunction "1_1") (pintype "unspecified"))
      (node (ref "C6") (pin "1") (pinfunction "1_1") (pintype "unspecified"))
      (node (ref "C8") (pin "1") (pinfunction "1_1") (pintype "unspecified"))
      (node (ref "DITCHING") (pin "4") (pinfunction "4_4") (pintype "unspecified"))
      (node (ref "DOME") (pin "2") (pinfunction "2_2") (pintype "input"))
      (node (ref "DRV-1K") (pin "1") (pinfunction "1_1") (pintype "unspecified"))
      (node (ref "EMEREXIT") (pin "2") (pinfunction "2_2") (pintype "input"))
      (node (ref "EMEREXITLT") (pin "4") (pinfunction "4_4") (pintype "unspecified"))
      (node (ref "ENG1AICE") (pin "4") (pinfunction "4_4") (pintype "unspecified"))
      (node (ref "ENG2AICE") (pin "4") (pinfunction "4_4") (pintype "unspecified"))
      (node (ref "FET-10K") (pin "1") (pinfunction "1_1") (pintype "unspecified"))
      (node (ref "INTEGLTPOT") (pin "1") (pinfunction "1_1") (pintype "unspecified"))
      (node (ref "LANDL") (pin "2") (pinfunction "2_2") (pintype "input"))
      (node (ref "LANDR") (pin "2") (pinfunction "2_2") (pintype "input"))
      (node (ref "LDGELEVPOT") (pin "1") (pinfunction "1_1") (pintype "unspecified"))
      (node (ref "MANVSCTL") (pin "2") (pinfunction "2_2") (pintype "input"))
      (node (ref "MODESEL") (pin "4") (pinfunction "4_4") (pintype "unspecified"))
      (node (ref "NAV&LOGO") (pin "2") (pinfunction "2_2") (pintype "input"))
      (node (ref "NOSE") (pin "2") (pinfunction "2_2") (pintype "input"))
      (node (ref "NOSMOKING") (pin "2") (pinfunction "2_2") (pintype "input"))
      (node (ref "P1") (pin "1") (pinfunction "GND_1") (pintype "unspecified"))
      (node (ref "PROBEWINDOW") (pin "4") (pinfunction "4_4") (pintype "unspecified"))
      (node (ref "Q1") (pin "3") (pinfunction "S_3") (pintype "unspecified"))
      (node (ref "R1") (pin "1") (pinfunction "1_1") (pintype "unspecified"))
      (node (ref "R2") (pin "1") (pinfunction "1_1") (pintype "unspecified"))
      (node (ref "R3") (pin "1") (pinfunction "1_1") (pintype "unspecified"))
      (node (ref "R4") (pin "1") (pinfunction "1_1") (pintype "unspecified"))
      (node (ref "R5") (pin "1") (pinfunction "1_1") (pintype "unspecified"))
      (node (ref "R7") (pin "1") (pinfunction "1_1") (pintype "unspecified"))
      (node (ref "RUNWAYTURNOFF") (pin "2") (pinfunction "2_2") (pintype "input"))
      (node (ref "SEATBELTS") (pin "2") (pinfunction "2_2") (pintype "input"))
      (node (ref "SPARE") (pin "4") (pinfunction "4_4") (pintype "unspecified"))
      (node (ref "STBYCOMPASS") (pin "2") (pinfunction "2_2") (pintype "input"))
      (node (ref "STROBE") (pin "2") (pinfunction "2_2") (pintype "input"))
      (node (ref "U1") (pin "43") (pinfunction "GND_43") (pintype "unspecified"))
      (node (ref "U1") (pin "83") (pinfunction "GND_83") (pintype "unspecified"))
      (node (ref "U1") (pin "84") (pinfunction "GND_84") (pintype "unspecified"))
      (node (ref "U2") (pin "1") (pinfunction "GND_1") (pintype "passive"))
      (node (ref "U3") (pin "1") (pinfunction "GND_1") (pintype "passive"))
      (node (ref "U4") (pin "1") (pinfunction "GND_1") (pintype "passive"))
      (node (ref "U5") (pin "1") (pinfunction "GND_1") (pintype "passive"))
      (node (ref "U6") (pin "1") (pinfunction "GND_1") (pintype "unspecified"))
      (node (ref "U7") (pin "1") (pinfunction "GND_1") (pintype "unspecified"))
      (node (ref "U8") (pin "1") (pinfunction "GND_1") (pintype "unspecified"))
      (node (ref "WING") (pin "2") (pinfunction "2_2") (pintype "input"))
      (node (ref "WINGAICE") (pin "4") (pinfunction "4_4") (pintype "unspecified"))
    )
    (net (code "37") (name "LEDDRV_CLK") (class "Default")
      (node (ref "U1") (pin "2") (pinfunction "A1_2") (pintype "unspecified"))
      (node (ref "U2") (pin "3") (pinfunction "CLK_3") (pintype "unspecified"))
      (node (ref "U3") (pin "3") (pinfunction "CLK_3") (pintype "unspecified"))
      (node (ref "U4") (pin "3") (pinfunction "CLK_3") (pintype "unspecified"))
      (node (ref "U5") (pin "3") (pinfunction "CLK_3") (pintype "unspecified"))
      (node (ref "U6") (pin "3") (pinfunction "CLK_3") (pintype "unspecified"))
      (node (ref "U7") (pin "3") (pinfunction "CLK_3") (pintype "unspecified"))
      (node (ref "U8") (pin "3") (pinfunction "CLK_3") (pintype "unspecified"))
    )
    (net (code "38") (name "LEDDRV_DATA") (class "Default")
      (node (ref "U1") (pin "3") (pinfunction "A2_3") (pintype "unspecified"))
      (node (ref "U2") (pin "2") (pinfunction "SDI_2") (pintype "unspecified"))
      (node (ref "U8") (pin "2") (pinfunction "SDI_2") (pintype "unspecified"))
    )
    (net (code "39") (name "LEDDRV_DATA_2") (class "Default")
      (node (ref "U2") (pin "14") (pinfunction "SDO_14") (pintype "output"))
      (node (ref "U3") (pin "2") (pinfunction "SDI_2") (pintype "unspecified"))
      (node (ref "U6") (pin "2") (pinfunction "SDI_2") (pintype "unspecified"))
      (node (ref "U8") (pin "22") (pinfunction "SDO_22") (pintype "unspecified"))
    )
    (net (code "40") (name "LEDDRV_DATA_3") (class "Default")
      (node (ref "U3") (pin "14") (pinfunction "SDO_14") (pintype "output"))
      (node (ref "U4") (pin "2") (pinfunction "SDI_2") (pintype "unspecified"))
      (node (ref "U6") (pin "22") (pinfunction "SDO_22") (pintype "unspecified"))
      (node (ref "U7") (pin "2") (pinfunction "SDI_2") (pintype "unspecified"))
    )
    (net (code "41") (name "LEDDRV_DATA_4") (class "Default")
      (node (ref "U4") (pin "14") (pinfunction "SDO_14") (pintype "output"))
      (node (ref "U5") (pin "2") (pinfunction "SDI_2") (pintype "unspecified"))
    )
    (net (code "42") (name "LEDDRV_LATCH") (class "Default")
      (node (ref "U1") (pin "1") (pinfunction "A0_1") (pintype "unspecified"))
      (node (ref "U2") (pin "4") (pinfunction "LE(ED1)_4") (pintype "unspecified"))
      (node (ref "U3") (pin "4") (pinfunction "LE(ED1)_4") (pintype "unspecified"))
      (node (ref "U4") (pin "4") (pinfunction "LE(ED1)_4") (pintype "unspecified"))
      (node (ref "U5") (pin "4") (pinfunction "LE(ED1)_4") (pintype "unspecified"))
      (node (ref "U6") (pin "4") (pinfunction "LE_4") (pintype "unspecified"))
      (node (ref "U7") (pin "4") (pinfunction "LE_4") (pintype "unspecified"))
      (node (ref "U8") (pin "4") (pinfunction "LE_4") (pintype "unspecified"))
    )
    (net (code "43") (name "Net-(BL_LED1-Pad2)") (class "Default")
      (node (ref "BL_LED1") (pin "2") (pinfunction "2_2") (pintype "unspecified"))
      (node (ref "BL_LED2") (pin "1") (pinfunction "1_1") (pintype "unspecified"))
    )
    (net (code "44") (name "Net-(BL_LED2-Pad2)") (class "Default")
      (node (ref "BL_LED2") (pin "2") (pinfunction "2_2") (pintype "unspecified"))
      (node (ref "BL_LED7") (pin "1") (pinfunction "1_1") (pintype "unspecified"))
    )
    (net (code "45") (name "Net-(BL_LED3-Pad2)") (class "Default")
      (node (ref "BL_LED3") (pin "2") (pinfunction "2_2") (pintype "unspecified"))
      (node (ref "BL_LED4") (pin "1") (pinfunction "1_1") (pintype "unspecified"))
    )
    (net (code "46") (name "Net-(BL_LED4-Pad2)") (class "Default")
      (node (ref "BL_LED4") (pin "2") (pinfunction "2_2") (pintype "unspecified"))
      (node (ref "BL_LED5") (pin "1") (pinfunction "1_1") (pintype "unspecified"))
    )
    (net (code "47") (name "Net-(BL_LED5-Pad2)") (class "Default")
      (node (ref "BL_LED5") (pin "2") (pinfunction "2_2") (pintype "unspecified"))
      (node (ref "BL_LED6") (pin "1") (pinfunction "1_1") (pintype "unspecified"))
    )
    (net (code "48") (name "Net-(BL_LED7-Pad2)") (class "Default")
      (node (ref "BL_LED7") (pin "2") (pinfunction "2_2") (pintype "unspecified"))
      (node (ref "BL_LED8") (pin "1") (pinfunction "1_1") (pintype "unspecified"))
    )
    (net (code "49") (name "Net-(BL_LED10-Pad1)") (class "Default")
      (node (ref "BL_LED10") (pin "1") (pinfunction "1_1") (pintype "unspecified"))
      (node (ref "BL_LED11") (pin "2") (pinfunction "2_2") (pintype "unspecified"))
    )
    (net (code "50") (name "Net-(BL_LED10-Pad2)") (class "Default")
      (node (ref "BL_LED10") (pin "2") (pinfunction "2_2") (pintype "unspecified"))
      (node (ref "BL_LED9") (pin "1") (pinfunction "1_1") (pintype "unspecified"))
    )
    (net (code "51") (name "Net-(BL_LED11-Pad1)") (class "Default")
      (node (ref "BL_LED11") (pin "1") (pinfunction "1_1") (pintype "unspecified"))
      (node (ref "BL_LED12") (pin "2") (pinfunction "2_2") (pintype "unspecified"))
    )
    (net (code "52") (name "Net-(BL_LED13-Pad1)") (class "Default")
      (node (ref "BL_LED13") (pin "1") (pinfunction "1_1") (pintype "unspecified"))
      (node (ref "BL_LED14") (pin "2") (pinfunction "2_2") (pintype "unspecified"))
    )
    (net (code "53") (name "Net-(BL_LED14-Pad1)") (class "Default")
      (node (ref "BL_LED14") (pin "1") (pinfunction "1_1") (pintype "unspecified"))
      (node (ref "BL_LED15") (pin "2") (pinfunction "2_2") (pintype "unspecified"))
    )
    (net (code "54") (name "Net-(BL_LED15-Pad1)") (class "Default")
      (node (ref "BL_LED15") (pin "1") (pinfunction "1_1") (pintype "unspecified"))
      (node (ref "BL_LED16") (pin "2") (pinfunction "2_2") (pintype "unspecified"))
    )
    (net (code "55") (name "Net-(BL_LED17-Pad2)") (class "Default")
      (node (ref "BL_LED17") (pin "2") (pinfunction "2_2") (pintype "unspecified"))
      (node (ref "BL_LED18") (pin "1") (pinfunction "1_1") (pintype "unspecified"))
    )
    (net (code "56") (name "Net-(BL_LED18-Pad2)") (class "Default")
      (node (ref "BL_LED18") (pin "2") (pinfunction "2_2") (pintype "unspecified"))
      (node (ref "BL_LED19") (pin "1") (pinfunction "1_1") (pintype "unspecified"))
    )
    (net (code "57") (name "Net-(BL_LED19-Pad2)") (class "Default")
      (node (ref "BL_LED19") (pin "2") (pinfunction "2_2") (pintype "unspecified"))
      (node (ref "BL_LED20") (pin "1") (pinfunction "1_1") (pintype "unspecified"))
    )
    (net (code "58") (name "Net-(BL_LED21-Pad1)") (class "Default")
      (node (ref "BL_LED21") (pin "1") (pinfunction "1_1") (pintype "unspecified"))
      (node (ref "BL_LED22") (pin "2") (pinfunction "2_2") (pintype "unspecified"))
    )
    (net (code "59") (name "Net-(BL_LED22-Pad1)") (class "Default")
      (node (ref "BL_LED22") (pin "1") (pinfunction "1_1") (pintype "unspecified"))
      (node (ref "BL_LED23") (pin "2") (pinfunction "2_2") (pintype "unspecified"))
    )
    (net (code "60") (name "Net-(BL_LED23-Pad1)") (class "Default")
      (node (ref "BL_LED23") (pin "1") (pinfunction "1_1") (pintype "unspecified"))
      (node (ref "BL_LED24") (pin "2") (pinfunction "2_2") (pintype "unspecified"))
    )
    (net (code "61") (name "Net-(BL_LED25-Pad2)") (class "Default")
      (node (ref "BL_LED25") (pin "2") (pinfunction "2_2") (pintype "unspecified"))
      (node (ref "BL_LED26") (pin "1") (pinfunction "1_1") (pintype "unspecified"))
    )
    (net (code "62") (name "Net-(BL_LED26-Pad2)") (class "Default")
      (node (ref "BL_LED26") (pin "2") (pinfunction "2_2") (pintype "unspecified"))
      (node (ref "BL_LED27") (pin "1") (pinfunction "1_1") (pintype "unspecified"))
    )
    (net (code "63") (name "Net-(BL_LED27-Pad2)") (class "Default")
      (node (ref "BL_LED27") (pin "2") (pinfunction "2_2") (pintype "unspecified"))
      (node (ref "BL_LED28") (pin "1") (pinfunction "1_1") (pintype "unspecified"))
    )
    (net (code "64") (name "Net-(BL_LED29-Pad1)") (class "Default")
      (node (ref "BL_LED29") (pin "1") (pinfunction "1_1") (pintype "unspecified"))
      (node (ref "BL_LED30") (pin "2") (pinfunction "2_2") (pintype "unspecified"))
    )
    (net (code "65") (name "Net-(BL_LED30-Pad1)") (class "Default")
      (node (ref "BL_LED30") (pin "1") (pinfunction "1_1") (pintype "unspecified"))
      (node (ref "BL_LED31") (pin "2") (pinfunction "2_2") (pintype "unspecified"))
    )
    (net (code "66") (name "Net-(BL_LED31-Pad1)") (class "Default")
      (node (ref "BL_LED31") (pin "1") (pinfunction "1_1") (pintype "unspecified"))
      (node (ref "BL_LED32") (pin "2") (pinfunction "2_2") (pintype "unspecified"))
    )
    (net (code "67") (name "Net-(Q1-D)") (class "Default")
      (node (ref "Q1") (pin "2") (pinfunction "D_2") (pintype "unspecified"))
      (node (ref "R10-330") (pin "2") (pinfunction "2_2") (pintype "unspecified"))
      (node (ref "R3-330") (pin "2") (pinfunction "2_2") (pintype "unspecified"))
      (node (ref "R4-330") (pin "2") (pinfunction "2_2") (pintype "unspecified"))
      (node (ref "R5-330") (pin "2") (pinfunction "2_2") (pintype "unspecified"))
      (node (ref "R6-330") (pin "2") (pinfunction "2_2") (pintype "unspecified"))
      (node (ref "R7-330") (pin "2") (pinfunction "2_2") (pintype "unspecified"))
      (node (ref "R8-330") (pin "2") (pinfunction "2_2") (pintype "unspecified"))
      (node (ref "R9-330") (pin "2") (pinfunction "2_2") (pintype "unspecified"))
    )
    (net (code "68") (name "Net-(Q1-G)") (class "Default")
      (node (ref "FET-10K") (pin "2") (pinfunction "2_2") (pintype "unspecified"))
      (node (ref "FET-1K") (pin "1") (pinfunction "1_1") (pintype "unspecified"))
      (node (ref "Q1") (pin "1") (pinfunction "G_1") (pintype "unspecified"))
    )
    (net (code "69") (name "Net-(U2-R-EXT)") (class "Default")
      (node (ref "R1") (pin "2") (pinfunction "2_2") (pintype "unspecified"))
      (node (ref "U2") (pin "15") (pinfunction "R-EXT_15") (pintype "unspecified"))
    )
    (net (code "70") (name "Net-(U3-R-EXT)") (class "Default")
      (node (ref "R2") (pin "2") (pinfunction "2_2") (pintype "unspecified"))
      (node (ref "U3") (pin "15") (pinfunction "R-EXT_15") (pintype "unspecified"))
    )
    (net (code "71") (name "Net-(U4-R-EXT)") (class "Default")
      (node (ref "R3") (pin "2") (pinfunction "2_2") (pintype "unspecified"))
      (node (ref "U4") (pin "15") (pinfunction "R-EXT_15") (pintype "unspecified"))
    )
    (net (code "72") (name "Net-(U5-R-EXT)") (class "Default")
      (node (ref "DRV-1K") (pin "2") (pinfunction "2_2") (pintype "unspecified"))
      (node (ref "U5") (pin "15") (pinfunction "R-EXT_15") (pintype "unspecified"))
    )
    (net (code "73") (name "Net-(U6-REXT)") (class "Default")
      (node (ref "R7") (pin "2") (pinfunction "2_2") (pintype "unspecified"))
      (node (ref "U6") (pin "23") (pinfunction "REXT_23") (pintype "unspecified"))
    )
    (net (code "74") (name "Net-(U7-REXT)") (class "Default")
      (node (ref "R5") (pin "2") (pinfunction "2_2") (pintype "unspecified"))
      (node (ref "U7") (pin "23") (pinfunction "REXT_23") (pintype "unspecified"))
    )
    (net (code "75") (name "Net-(U8-REXT)") (class "Default")
      (node (ref "R4") (pin "2") (pinfunction "2_2") (pintype "unspecified"))
      (node (ref "U8") (pin "23") (pinfunction "REXT_23") (pintype "unspecified"))
    )
    (net (code "76") (name "annunbrt") (class "Default")
      (node (ref "ANNUN") (pin "3") (pinfunction "3_3") (pintype "input"))
      (node (ref "U1") (pin "18") (pinfunction "D33_18") (pintype "unspecified"))
    )
    (net (code "77") (name "annunoff") (class "Default")
      (node (ref "ANNUN") (pin "1") (pinfunction "1_1") (pintype "input"))
      (node (ref "U1") (pin "19") (pinfunction "D34_19") (pintype "unspecified"))
    )
    (net (code "78") (name "apumaster") (class "Default")
      (node (ref "APUMASTER") (pin "1") (pinfunction "1_1") (pintype "unspecified"))
      (node (ref "U1") (pin "71") (pinfunction "D5_71") (pintype "unspecified"))
    )
    (net (code "79") (name "apumasterfault") (class "Default")
      (node (ref "APUMASTERFAULT") (pin "2") (pinfunction "2_2") (pintype "unspecified"))
      (node (ref "U3") (pin "9") (pinfunction "OUT4_9") (pintype "output"))
      (node (ref "U8") (pin "17") (pinfunction "OUT12_17") (pintype "unspecified"))
    )
    (net (code "80") (name "apumasteron") (class "Default")
      (node (ref "APUMASTERON") (pin "2") (pinfunction "2_2") (pintype "unspecified"))
      (node (ref "U3") (pin "10") (pinfunction "OUT5_10") (pintype "output"))
      (node (ref "U8") (pin "18") (pinfunction "OUT13_18") (pintype "unspecified"))
    )
    (net (code "81") (name "apustart") (class "Default")
      (node (ref "APUSTART") (pin "1") (pinfunction "1_1") (pintype "unspecified"))
      (node (ref "U1") (pin "72") (pinfunction "D4_72") (pintype "unspecified"))
    )
    (net (code "82") (name "apustartfault") (class "Default")
      (node (ref "APUSTARTFAULT") (pin "2") (pinfunction "2_2") (pintype "unspecified"))
      (node (ref "U3") (pin "11") (pinfunction "OUT6_11") (pintype "output"))
      (node (ref "U8") (pin "19") (pinfunction "OUT14_19") (pintype "unspecified"))
    )
    (net (code "83") (name "apustarton") (class "Default")
      (node (ref "APUSTARTON") (pin "2") (pinfunction "2_2") (pintype "unspecified"))
      (node (ref "U3") (pin "12") (pinfunction "OUT7_12") (pintype "output"))
      (node (ref "U8") (pin "20") (pinfunction "OUT15_20") (pintype "unspecified"))
    )
    (net (code "84") (name "beaconon") (class "Default")
      (node (ref "BEACON") (pin "3") (pinfunction "3_3") (pintype "input"))
      (node (ref "U1") (pin "61") (pinfunction "D15_61") (pintype "unspecified"))
    )
    (net (code "85") (name "ditching") (class "Default")
      (node (ref "DITCHING") (pin "1") (pinfunction "1_1") (pintype "unspecified"))
      (node (ref "U1") (pin "26") (pinfunction "D41_26") (pintype "unspecified"))
    )
    (net (code "86") (name "ditchingfault") (class "Default")
      (node (ref "DITCHINGFAULT") (pin "2") (pinfunction "2_2") (pintype "unspecified"))
      (node (ref "U4") (pin "5") (pinfunction "OUT0_5") (pintype "output"))
      (node (ref "U6") (pin "5") (pinfunction "OUT0_5") (pintype "unspecified"))
    )
    (net (code "87") (name "ditchingon") (class "Default")
      (node (ref "DITCHINGON") (pin "2") (pinfunction "2_2") (pintype "unspecified"))
      (node (ref "U4") (pin "6") (pinfunction "OUT1_6") (pintype "output"))
      (node (ref "U6") (pin "6") (pinfunction "OUT1_6") (pintype "unspecified"))
    )
    (net (code "88") (name "domebrt") (class "Default")
      (node (ref "DOME") (pin "3") (pinfunction "3_3") (pintype "input"))
      (node (ref "U1") (pin "16") (pinfunction "A15_16") (pintype "unspecified"))
    )
    (net (code "89") (name "domedim") (class "Default")
      (node (ref "DOME") (pin "1") (pinfunction "1_1") (pintype "input"))
      (node (ref "U1") (pin "17") (pinfunction "D32_17") (pintype "unspecified"))
    )
    (net (code "90") (name "emerexitlt") (class "Default")
      (node (ref "EMEREXITLT") (pin "1") (pinfunction "1_1") (pintype "unspecified"))
      (node (ref "U1") (pin "12") (pinfunction "A11_12") (pintype "unspecified"))
    )
    (net (code "91") (name "emerexitltfault") (class "Default")
      (node (ref "EMEREXITLTFAULT") (pin "2") (pinfunction "2_2") (pintype "unspecified"))
      (node (ref "U4") (pin "7") (pinfunction "OUT2_7") (pintype "output"))
      (node (ref "U6") (pin "7") (pinfunction "OUT2_7") (pintype "unspecified"))
    )
    (net (code "92") (name "emerexitltoff") (class "Default")
      (node (ref "EMEREXITLTOFF") (pin "2") (pinfunction "2_2") (pintype "unspecified"))
      (node (ref "U4") (pin "8") (pinfunction "OUT3_8") (pintype "output"))
      (node (ref "U6") (pin "8") (pinfunction "OUT3_8") (pintype "unspecified"))
    )
    (net (code "93") (name "emerexitoff") (class "Default")
      (node (ref "EMEREXIT") (pin "1") (pinfunction "1_1") (pintype "input"))
      (node (ref "U1") (pin "14") (pinfunction "A13_14") (pintype "unspecified"))
    )
    (net (code "94") (name "emerexiton") (class "Default")
      (node (ref "EMEREXIT") (pin "3") (pinfunction "3_3") (pintype "input"))
      (node (ref "U1") (pin "13") (pinfunction "A12_13") (pintype "unspecified"))
    )
    (net (code "95") (name "eng1aice") (class "Default")
      (node (ref "ENG1AICE") (pin "1") (pinfunction "1_1") (pintype "unspecified"))
      (node (ref "U1") (pin "20") (pinfunction "D35_20") (pintype "unspecified"))
    )
    (net (code "96") (name "eng1aicefault") (class "Default")
      (node (ref "ENG1AICEFAULT") (pin "2") (pinfunction "2_2") (pintype "unspecified"))
      (node (ref "U2") (pin "9") (pinfunction "OUT4_9") (pintype "output"))
      (node (ref "U8") (pin "9") (pinfunction "OUT4_9") (pintype "unspecified"))
    )
    (net (code "97") (name "eng1aiceon") (class "Default")
      (node (ref "ENG1AICEON") (pin "2") (pinfunction "2_2") (pintype "unspecified"))
      (node (ref "U2") (pin "10") (pinfunction "OUT5_10") (pintype "output"))
      (node (ref "U8") (pin "10") (pinfunction "OUT5_10") (pintype "unspecified"))
    )
    (net (code "98") (name "eng2aice") (class "Default")
      (node (ref "ENG2AICE") (pin "1") (pinfunction "1_1") (pintype "unspecified"))
      (node (ref "U1") (pin "21") (pinfunction "D36_21") (pintype "unspecified"))
    )
    (net (code "99") (name "eng2aicefault") (class "Default")
      (node (ref "ENG2AICEFAULT") (pin "2") (pinfunction "2_2") (pintype "unspecified"))
      (node (ref "U2") (pin "11") (pinfunction "OUT6_11") (pintype "output"))
      (node (ref "U8") (pin "11") (pinfunction "OUT6_11") (pintype "unspecified"))
    )
    (net (code "100") (name "eng2aiceon") (class "Default")
      (node (ref "ENG2AICEON") (pin "2") (pinfunction "2_2") (pintype "unspecified"))
      (node (ref "U2") (pin "12") (pinfunction "OUT7_12") (pintype "output"))
      (node (ref "U8") (pin "12") (pinfunction "OUT7_12") (pintype "unspecified"))
    )
    (net (code "101") (name "integltpot") (class "Default")
      (node (ref "INTEGLTPOT") (pin "2") (pinfunction "2_2") (pintype "unspecified"))
      (node (ref "U1") (pin "5") (pinfunction "A4_5") (pintype "unspecified"))
    )
    (net (code "102") (name "landlon") (class "Default")
      (node (ref "LANDL") (pin "3") (pinfunction "3_3") (pintype "input"))
      (node (ref "U1") (pin "59") (pinfunction "D17_59") (pintype "unspecified"))
    )
    (net (code "103") (name "landlretract") (class "Default")
      (node (ref "LANDL") (pin "1") (pinfunction "1_1") (pintype "input"))
      (node (ref "U1") (pin "60") (pinfunction "D16_60") (pintype "unspecified"))
    )
    (net (code "104") (name "landron") (class "Default")
      (node (ref "LANDR") (pin "3") (pinfunction "3_3") (pintype "input"))
      (node (ref "U1") (pin "62") (pinfunction "D14_62") (pintype "unspecified"))
    )
    (net (code "105") (name "landrretract") (class "Default")
      (node (ref "LANDR") (pin "1") (pinfunction "1_1") (pintype "input"))
      (node (ref "U1") (pin "64") (pinfunction "D12_64") (pintype "unspecified"))
    )
    (net (code "106") (name "ldgelevpot") (class "Default")
      (node (ref "LDGELEVPOT") (pin "2") (pinfunction "2_2") (pintype "unspecified"))
      (node (ref "U1") (pin "4") (pinfunction "A3_4") (pintype "unspecified"))
    )
    (net (code "107") (name "manvsctloff") (class "Default")
      (node (ref "MANVSCTL") (pin "1") (pinfunction "1_1") (pintype "input"))
      (node (ref "U1") (pin "24") (pinfunction "D39_24") (pintype "unspecified"))
    )
    (net (code "108") (name "manvsctlon") (class "Default")
      (node (ref "MANVSCTL") (pin "3") (pinfunction "3_3") (pintype "input"))
      (node (ref "U1") (pin "23") (pinfunction "D38_23") (pintype "unspecified"))
    )
    (net (code "109") (name "modesel") (class "Default")
      (node (ref "MODESEL") (pin "1") (pinfunction "1_1") (pintype "unspecified"))
      (node (ref "U1") (pin "25") (pinfunction "D40_25") (pintype "unspecified"))
    )
    (net (code "110") (name "modeselfault") (class "Default")
      (node (ref "MODESELFAULT") (pin "2") (pinfunction "2_2") (pintype "unspecified"))
      (node (ref "U3") (pin "7") (pinfunction "OUT2_7") (pintype "output"))
      (node (ref "U8") (pin "15") (pinfunction "OUT10_15") (pintype "unspecified"))
    )
    (net (code "111") (name "modeselon") (class "Default")
      (node (ref "MODESELON") (pin "2") (pinfunction "2_2") (pintype "unspecified"))
      (node (ref "U3") (pin "8") (pinfunction "OUT3_8") (pintype "output"))
      (node (ref "U8") (pin "16") (pinfunction "OUT11_16") (pintype "unspecified"))
    )
    (net (code "112") (name "nav&logooff") (class "Default")
      (node (ref "NAV&LOGO") (pin "1") (pinfunction "1_1") (pintype "input"))
      (node (ref "U1") (pin "69") (pinfunction "D7_69") (pintype "unspecified"))
    )
    (net (code "113") (name "nav&logoon") (class "Default")
      (node (ref "NAV&LOGO") (pin "3") (pinfunction "3_3") (pintype "input"))
      (node (ref "U1") (pin "68") (pinfunction "D8_68") (pintype "unspecified"))
    )
    (net (code "114") (name "noseoff") (class "Default")
      (node (ref "NOSE") (pin "1") (pinfunction "1_1") (pintype "input"))
      (node (ref "U1") (pin "67") (pinfunction "D9_67") (pintype "unspecified"))
    )
    (net (code "115") (name "noseon") (class "Default")
      (node (ref "NOSE") (pin "3") (pinfunction "3_3") (pintype "input"))
      (node (ref "U1") (pin "66") (pinfunction "D10_66") (pintype "unspecified"))
    )
    (net (code "116") (name "nosmokingoff") (class "Default")
      (node (ref "NOSMOKING") (pin "1") (pinfunction "1_1") (pintype "input"))
      (node (ref "U1") (pin "11") (pinfunction "A10_11") (pintype "unspecified"))
    )
    (net (code "117") (name "nosmokingon") (class "Default")
      (node (ref "NOSMOKING") (pin "3") (pinfunction "3_3") (pintype "input"))
      (node (ref "U1") (pin "10") (pinfunction "A9_10") (pintype "unspecified"))
    )
    (net (code "118") (name "probewindow") (class "Default")
      (node (ref "PROBEWINDOW") (pin "1") (pinfunction "1_1") (pintype "unspecified"))
      (node (ref "U1") (pin "22") (pinfunction "D37_22") (pintype "unspecified"))
    )
    (net (code "119") (name "probewindowfault") (class "Default")
      (node (ref "PROBEWINDOWFAULT") (pin "2") (pinfunction "2_2") (pintype "unspecified"))
      (node (ref "U3") (pin "5") (pinfunction "OUT0_5") (pintype "output"))
      (node (ref "U8") (pin "13") (pinfunction "OUT8_13") (pintype "unspecified"))
    )
    (net (code "120") (name "probewindowoff") (class "Default")
      (node (ref "PROBEWINDOWOFF") (pin "2") (pinfunction "2_2") (pintype "unspecified"))
      (node (ref "U3") (pin "6") (pinfunction "OUT1_6") (pintype "output"))
      (node (ref "U8") (pin "14") (pinfunction "OUT9_14") (pintype "unspecified"))
    )
    (net (code "121") (name "runwayturnoffon") (class "Default")
      (node (ref "RUNWAYTURNOFF") (pin "3") (pinfunction "3_3") (pintype "input"))
      (node (ref "U1") (pin "58") (pinfunction "D18_58") (pintype "unspecified"))
    )
    (net (code "122") (name "seatbeltson") (class "Default")
      (node (ref "SEATBELTS") (pin "3") (pinfunction "3_3") (pintype "input"))
      (node (ref "U1") (pin "9") (pinfunction "A8_9") (pintype "unspecified"))
    )
    (net (code "123") (name "spare") (class "Default")
      (node (ref "SPARE") (pin "1") (pinfunction "1_1") (pintype "unspecified"))
      (node (ref "U1") (pin "70") (pinfunction "D6_70") (pintype "unspecified"))
    )
    (net (code "124") (name "sparefault") (class "Default")
      (node (ref "SPAREFAULT") (pin "2") (pinfunction "2_2") (pintype "unspecified"))
      (node (ref "U2") (pin "7") (pinfunction "OUT2_7") (pintype "output"))
      (node (ref "U8") (pin "7") (pinfunction "OUT2_7") (pintype "unspecified"))
    )
    (net (code "125") (name "spareon") (class "Default")
      (node (ref "SPAREON") (pin "2") (pinfunction "2_2") (pintype "unspecified"))
      (node (ref "U2") (pin "8") (pinfunction "OUT3_8") (pintype "output"))
      (node (ref "U8") (pin "8") (pinfunction "OUT3_8") (pintype "unspecified"))
    )
    (net (code "126") (name "stbycompasson") (class "Default")
      (node (ref "STBYCOMPASS") (pin "3") (pinfunction "3_3") (pintype "input"))
      (node (ref "U1") (pin "15") (pinfunction "A14_15") (pintype "unspecified"))
    )
    (net (code "127") (name "strobeoff") (class "Default")
      (node (ref "STROBE") (pin "1") (pinfunction "1_1") (pintype "input"))
      (node (ref "U1") (pin "45") (pinfunction "D31_45") (pintype "unspecified"))
    )
    (net (code "128") (name "strobeon") (class "Default")
      (node (ref "STROBE") (pin "3") (pinfunction "3_3") (pintype "input"))
      (node (ref "U1") (pin "57") (pinfunction "D19_57") (pintype "unspecified"))
    )
    (net (code "129") (name "unconnected-(APUMASTER-Pad2)") (class "Default")
      (node (ref "APUMASTER") (pin "2") (pinfunction "2_2") (pintype "unspecified+no_connect"))
    )
    (net (code "130") (name "unconnected-(APUMASTER-Pad3)") (class "Default")
      (node (ref "APUMASTER") (pin "3") (pinfunction "3_3") (pintype "unspecified+no_connect"))
    )
    (net (code "131") (name "unconnected-(APUSTART-Pad2)") (class "Default")
      (node (ref "APUSTART") (pin "2") (pinfunction "2_2") (pintype "unspecified+no_connect"))
    )
    (net (code "132") (name "unconnected-(APUSTART-Pad3)") (class "Default")
      (node (ref "APUSTART") (pin "3") (pinfunction "3_3") (pintype "unspecified+no_connect"))
    )
    (net (code "133") (name "unconnected-(BEACON-Pad1)") (class "Default")
      (node (ref "BEACON") (pin "1") (pinfunction "1_1") (pintype "input+no_connect"))
    )
    (net (code "134") (name "unconnected-(DITCHING-Pad2)") (class "Default")
      (node (ref "DITCHING") (pin "2") (pinfunction "2_2") (pintype "unspecified+no_connect"))
    )
    (net (code "135") (name "unconnected-(DITCHING-Pad3)") (class "Default")
      (node (ref "DITCHING") (pin "3") (pinfunction "3_3") (pintype "unspecified+no_connect"))
    )
    (net (code "136") (name "unconnected-(EMEREXITLT-Pad2)") (class "Default")
      (node (ref "EMEREXITLT") (pin "2") (pinfunction "2_2") (pintype "unspecified+no_connect"))
    )
    (net (code "137") (name "unconnected-(EMEREXITLT-Pad3)") (class "Default")
      (node (ref "EMEREXITLT") (pin "3") (pinfunction "3_3") (pintype "unspecified+no_connect"))
    )
    (net (code "138") (name "unconnected-(ENG1AICE-Pad2)") (class "Default")
      (node (ref "ENG1AICE") (pin "2") (pinfunction "2_2") (pintype "unspecified+no_connect"))
    )
    (net (code "139") (name "unconnected-(ENG1AICE-Pad3)") (class "Default")
      (node (ref "ENG1AICE") (pin "3") (pinfunction "3_3") (pintype "unspecified+no_connect"))
    )
    (net (code "140") (name "unconnected-(ENG2AICE-Pad2)") (class "Default")
      (node (ref "ENG2AICE") (pin "2") (pinfunction "2_2") (pintype "unspecified+no_connect"))
    )
    (net (code "141") (name "unconnected-(ENG2AICE-Pad3)") (class "Default")
      (node (ref "ENG2AICE") (pin "3") (pinfunction "3_3") (pintype "unspecified+no_connect"))
    )
    (net (code "142") (name "unconnected-(INTEGLTPOT-EH-Pad4)") (class "Default")
      (node (ref "INTEGLTPOT") (pin "4") (pinfunction "EH_4") (pintype "unspecified+no_connect"))
    )
    (net (code "143") (name "unconnected-(INTEGLTPOT-EH-Pad5)") (class "Default")
      (node (ref "INTEGLTPOT") (pin "5") (pinfunction "EH_5") (pintype "unspecified+no_connect"))
    )
    (net (code "144") (name "unconnected-(LDGELEVPOT-EH-Pad4)") (class "Default")
      (node (ref "LDGELEVPOT") (pin "4") (pinfunction "EH_4") (pintype "unspecified+no_connect"))
    )
    (net (code "145") (name "unconnected-(LDGELEVPOT-EH-Pad5)") (class "Default")
      (node (ref "LDGELEVPOT") (pin "5") (pinfunction "EH_5") (pintype "unspecified+no_connect"))
    )
    (net (code "146") (name "unconnected-(MODESEL-Pad2)") (class "Default")
      (node (ref "MODESEL") (pin "2") (pinfunction "2_2") (pintype "unspecified+no_connect"))
    )
    (net (code "147") (name "unconnected-(MODESEL-Pad3)") (class "Default")
      (node (ref "MODESEL") (pin "3") (pinfunction "3_3") (pintype "unspecified+no_connect"))
    )
    (net (code "148") (name "unconnected-(PROBEWINDOW-Pad2)") (class "Default")
      (node (ref "PROBEWINDOW") (pin "2") (pinfunction "2_2") (pintype "unspecified+no_connect"))
    )
    (net (code "149") (name "unconnected-(PROBEWINDOW-Pad3)") (class "Default")
      (node (ref "PROBEWINDOW") (pin "3") (pinfunction "3_3") (pintype "unspecified+no_connect"))
    )
    (net (code "150") (name "unconnected-(RUNWAYTURNOFF-Pad1)") (class "Default")
      (node (ref "RUNWAYTURNOFF") (pin "1") (pinfunction "1_1") (pintype "input+no_connect"))
    )
    (net (code "151") (name "unconnected-(SEATBELTS-Pad1)") (class "Default")
      (node (ref "SEATBELTS") (pin "1") (pinfunction "1_1") (pintype "input+no_connect"))
    )
    (net (code "152") (name "unconnected-(SPARE-Pad2)") (class "Default")
      (node (ref "SPARE") (pin "2") (pinfunction "2_2") (pintype "unspecified+no_connect"))
    )
    (net (code "153") (name "unconnected-(SPARE-Pad3)") (class "Default")
      (node (ref "SPARE") (pin "3") (pinfunction "3_3") (pintype "unspecified+no_connect"))
    )
    (net (code "154") (name "unconnected-(STBYCOMPASS-Pad1)") (class "Default")
      (node (ref "STBYCOMPASS") (pin "1") (pinfunction "1_1") (pintype "input+no_connect"))
    )
    (net (code "155") (name "unconnected-(U1-3.3V-Pad79)") (class "Default")
      (node (ref "U1") (pin "79") (pinfunction "3.3V_79") (pintype "unspecified+no_connect"))
    )
    (net (code "156") (name "unconnected-(U1-3.3V-Pad80)") (class "Default")
      (node (ref "U1") (pin "80") (pinfunction "3.3V_80") (pintype "unspecified+no_connect"))
    )
    (net (code "157") (name "unconnected-(U1-AREF-Pad78)") (class "Default")
      (node (ref "U1") (pin "78") (pinfunction "AREF_78") (pintype "unspecified+no_connect"))
    )
    (net (code "158") (name "unconnected-(U1-D13-Pad63)") (class "Default")
      (node (ref "U1") (pin "63") (pinfunction "D13_63") (pintype "unspecified+no_connect"))
    )
    (net (code "159") (name "unconnected-(U1-D29-Pad47)") (class "Default")
      (node (ref "U1") (pin "47") (pinfunction "D29_47") (pintype "unspecified+no_connect"))
    )
    (net (code "160") (name "unconnected-(U1-D30-Pad46)") (class "Default")
      (node (ref "U1") (pin "46") (pinfunction "D30_46") (pintype "unspecified+no_connect"))
    )
    (net (code "161") (name "unconnected-(U1-MISO-Pad40)") (class "Default")
      (node (ref "U1") (pin "40") (pinfunction "MISO_40") (pintype "unspecified+no_connect"))
    )
    (net (code "162") (name "unconnected-(U1-MOSI-Pad41)") (class "Default")
      (node (ref "U1") (pin "41") (pinfunction "MOSI_41") (pintype "unspecified+no_connect"))
    )
    (net (code "163") (name "unconnected-(U1-RX-Pad76)") (class "Default")
      (node (ref "U1") (pin "76") (pinfunction "RX_76") (pintype "unspecified+no_connect"))
    )
    (net (code "164") (name "unconnected-(U1-Reset-Pad44)") (class "Default")
      (node (ref "U1") (pin "44") (pinfunction "Reset_44") (pintype "unspecified+no_connect"))
    )
    (net (code "165") (name "unconnected-(U1-Reset-Pad77)") (class "Default")
      (node (ref "U1") (pin "77") (pinfunction "Reset_77") (pintype "unspecified+no_connect"))
    )
    (net (code "166") (name "unconnected-(U1-SCK-Pad42)") (class "Default")
      (node (ref "U1") (pin "42") (pinfunction "SCK_42") (pintype "unspecified+no_connect"))
    )
    (net (code "167") (name "unconnected-(U1-TX-Pad75)") (class "Default")
      (node (ref "U1") (pin "75") (pinfunction "TX_75") (pintype "unspecified+no_connect"))
    )
    (net (code "168") (name "unconnected-(U1-VIN-Pad85)") (class "Default")
      (node (ref "U1") (pin "85") (pinfunction "VIN_85") (pintype "unspecified+no_connect"))
    )
    (net (code "169") (name "unconnected-(U1-VIN-Pad86)") (class "Default")
      (node (ref "U1") (pin "86") (pinfunction "VIN_86") (pintype "unspecified+no_connect"))
    )
    (net (code "170") (name "unconnected-(U4-OUT4-Pad9)") (class "Default")
      (node (ref "U4") (pin "9") (pinfunction "OUT4_9") (pintype "output+no_connect"))
    )
    (net (code "171") (name "unconnected-(U4-OUT5-Pad10)") (class "Default")
      (node (ref "U4") (pin "10") (pinfunction "OUT5_10") (pintype "output+no_connect"))
    )
    (net (code "172") (name "unconnected-(U4-OUT6-Pad11)") (class "Default")
      (node (ref "U4") (pin "11") (pinfunction "OUT6_11") (pintype "output+no_connect"))
    )
    (net (code "173") (name "unconnected-(U4-OUT7-Pad12)") (class "Default")
      (node (ref "U4") (pin "12") (pinfunction "OUT7_12") (pintype "output+no_connect"))
    )
    (net (code "174") (name "unconnected-(U5-SDO-Pad14)") (class "Default")
      (node (ref "U5") (pin "14") (pinfunction "SDO_14") (pintype "output+no_connect"))
    )
    (net (code "175") (name "unconnected-(U6-OUT4-Pad9)") (class "Default")
      (node (ref "U6") (pin "9") (pinfunction "OUT4_9") (pintype "unspecified+no_connect"))
    )
    (net (code "176") (name "unconnected-(U6-OUT5-Pad10)") (class "Default")
      (node (ref "U6") (pin "10") (pinfunction "OUT5_10") (pintype "unspecified+no_connect"))
    )
    (net (code "177") (name "unconnected-(U6-OUT6-Pad11)") (class "Default")
      (node (ref "U6") (pin "11") (pinfunction "OUT6_11") (pintype "unspecified+no_connect"))
    )
    (net (code "178") (name "unconnected-(U6-OUT7-Pad12)") (class "Default")
      (node (ref "U6") (pin "12") (pinfunction "OUT7_12") (pintype "unspecified+no_connect"))
    )
    (net (code "179") (name "unconnected-(U6-OUT8-Pad13)") (class "Default")
      (node (ref "U6") (pin "13") (pinfunction "OUT8_13") (pintype "unspecified+no_connect"))
    )
    (net (code "180") (name "unconnected-(U6-OUT9-Pad14)") (class "Default")
      (node (ref "U6") (pin "14") (pinfunction "OUT9_14") (pintype "unspecified+no_connect"))
    )
    (net (code "181") (name "unconnected-(U6-OUT10-Pad15)") (class "Default")
      (node (ref "U6") (pin "15") (pinfunction "OUT10_15") (pintype "unspecified+no_connect"))
    )
    (net (code "182") (name "unconnected-(U6-OUT11-Pad16)") (class "Default")
      (node (ref "U6") (pin "16") (pinfunction "OUT11_16") (pintype "unspecified+no_connect"))
    )
    (net (code "183") (name "unconnected-(U6-OUT12-Pad17)") (class "Default")
      (node (ref "U6") (pin "17") (pinfunction "OUT12_17") (pintype "unspecified+no_connect"))
    )
    (net (code "184") (name "unconnected-(U6-OUT13-Pad18)") (class "Default")
      (node (ref "U6") (pin "18") (pinfunction "OUT13_18") (pintype "unspecified+no_connect"))
    )
    (net (code "185") (name "unconnected-(U6-OUT14-Pad19)") (class "Default")
      (node (ref "U6") (pin "19") (pinfunction "OUT14_19") (pintype "unspecified+no_connect"))
    )
    (net (code "186") (name "unconnected-(U6-OUT15-Pad20)") (class "Default")
      (node (ref "U6") (pin "20") (pinfunction "OUT15_20") (pintype "unspecified+no_connect"))
    )
    (net (code "187") (name "unconnected-(U7-OUT9-Pad14)") (class "Default")
      (node (ref "U7") (pin "14") (pinfunction "OUT9_14") (pintype "unspecified+no_connect"))
    )
    (net (code "188") (name "unconnected-(U7-OUT10-Pad15)") (class "Default")
      (node (ref "U7") (pin "15") (pinfunction "OUT10_15") (pintype "unspecified+no_connect"))
    )
    (net (code "189") (name "unconnected-(U7-OUT11-Pad16)") (class "Default")
      (node (ref "U7") (pin "16") (pinfunction "OUT11_16") (pintype "unspecified+no_connect"))
    )
    (net (code "190") (name "unconnected-(U7-OUT12-Pad17)") (class "Default")
      (node (ref "U7") (pin "17") (pinfunction "OUT12_17") (pintype "unspecified+no_connect"))
    )
    (net (code "191") (name "unconnected-(U7-OUT13-Pad18)") (class "Default")
      (node (ref "U7") (pin "18") (pinfunction "OUT13_18") (pintype "unspecified+no_connect"))
    )
    (net (code "192") (name "unconnected-(U7-OUT14-Pad19)") (class "Default")
      (node (ref "U7") (pin "19") (pinfunction "OUT14_19") (pintype "unspecified+no_connect"))
    )
    (net (code "193") (name "unconnected-(U7-OUT15-Pad20)") (class "Default")
      (node (ref "U7") (pin "20") (pinfunction "OUT15_20") (pintype "unspecified+no_connect"))
    )
    (net (code "194") (name "unconnected-(U7-SDO-Pad22)") (class "Default")
      (node (ref "U7") (pin "22") (pinfunction "SDO_22") (pintype "unspecified+no_connect"))
    )
    (net (code "195") (name "unconnected-(WING-Pad1)") (class "Default")
      (node (ref "WING") (pin "1") (pinfunction "1_1") (pintype "input+no_connect"))
    )
    (net (code "196") (name "unconnected-(WINGAICE-Pad2)") (class "Default")
      (node (ref "WINGAICE") (pin "2") (pinfunction "2_2") (pintype "unspecified+no_connect"))
    )
    (net (code "197") (name "unconnected-(WINGAICE-Pad3)") (class "Default")
      (node (ref "WINGAICE") (pin "3") (pinfunction "3_3") (pintype "unspecified+no_connect"))
    )
    (net (code "198") (name "wingaice") (class "Default")
      (node (ref "U1") (pin "56") (pinfunction "D20_56") (pintype "unspecified"))
      (node (ref "WINGAICE") (pin "1") (pinfunction "1_1") (pintype "unspecified"))
    )
    (net (code "199") (name "wingaicefault") (class "Default")
      (node (ref "U2") (pin "5") (pinfunction "OUT0_5") (pintype "output"))
      (node (ref "U8") (pin "5") (pinfunction "OUT0_5") (pintype "unspecified"))
      (node (ref "WINGAICEFAULT") (pin "2") (pinfunction "2_2") (pintype "unspecified"))
    )
    (net (code "200") (name "wingaiceon") (class "Default")
      (node (ref "U2") (pin "6") (pinfunction "OUT1_6") (pintype "output"))
      (node (ref "U8") (pin "6") (pinfunction "OUT1_6") (pintype "unspecified"))
      (node (ref "WINGAICEON") (pin "2") (pinfunction "2_2") (pintype "unspecified"))
    )
    (net (code "201") (name "wingon") (class "Default")
      (node (ref "U1") (pin "65") (pinfunction "D11_65") (pintype "unspecified"))
      (node (ref "WING") (pin "3") (pinfunction "3_3") (pintype "input"))
    )
  )
)
